# AK4493-Combi9.net
KiCad netlist of a schematic drawn in EAGLE
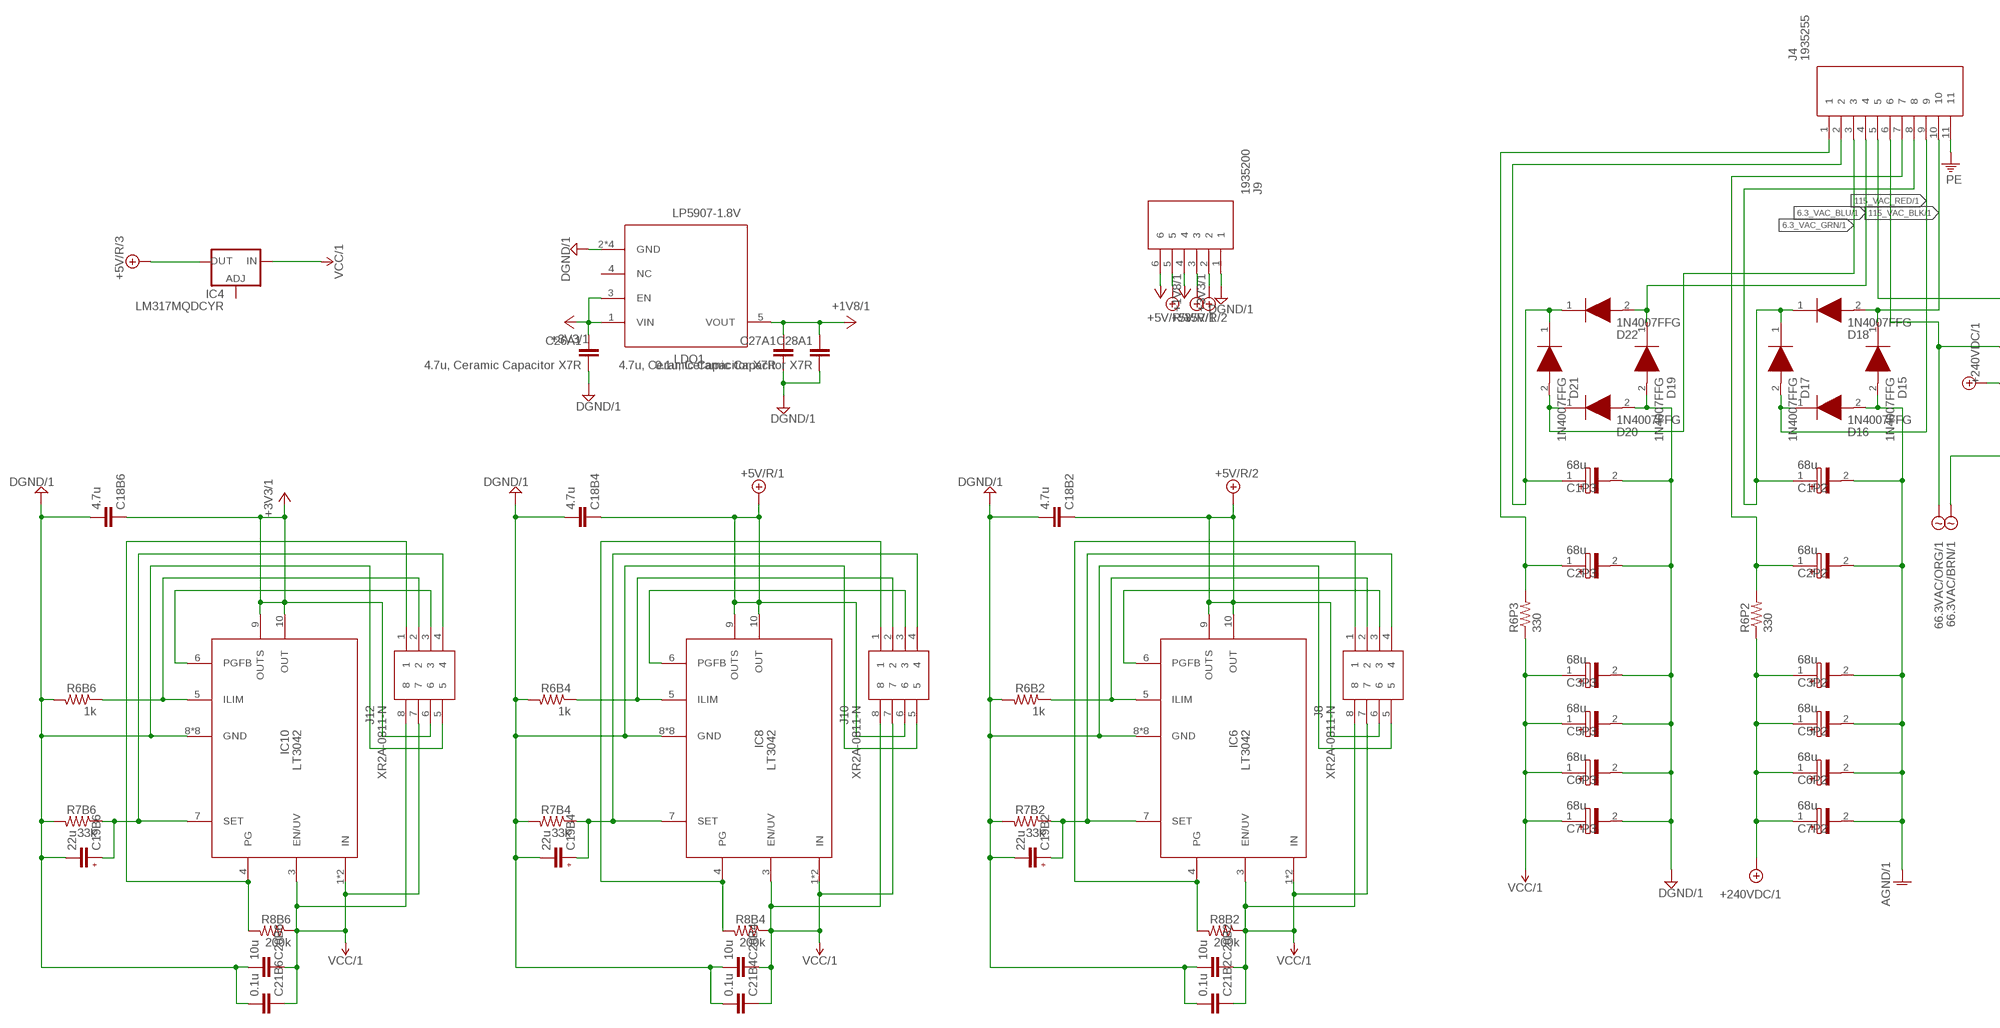
[diagram p0: schematic, sheet 1, part 1 of 3]
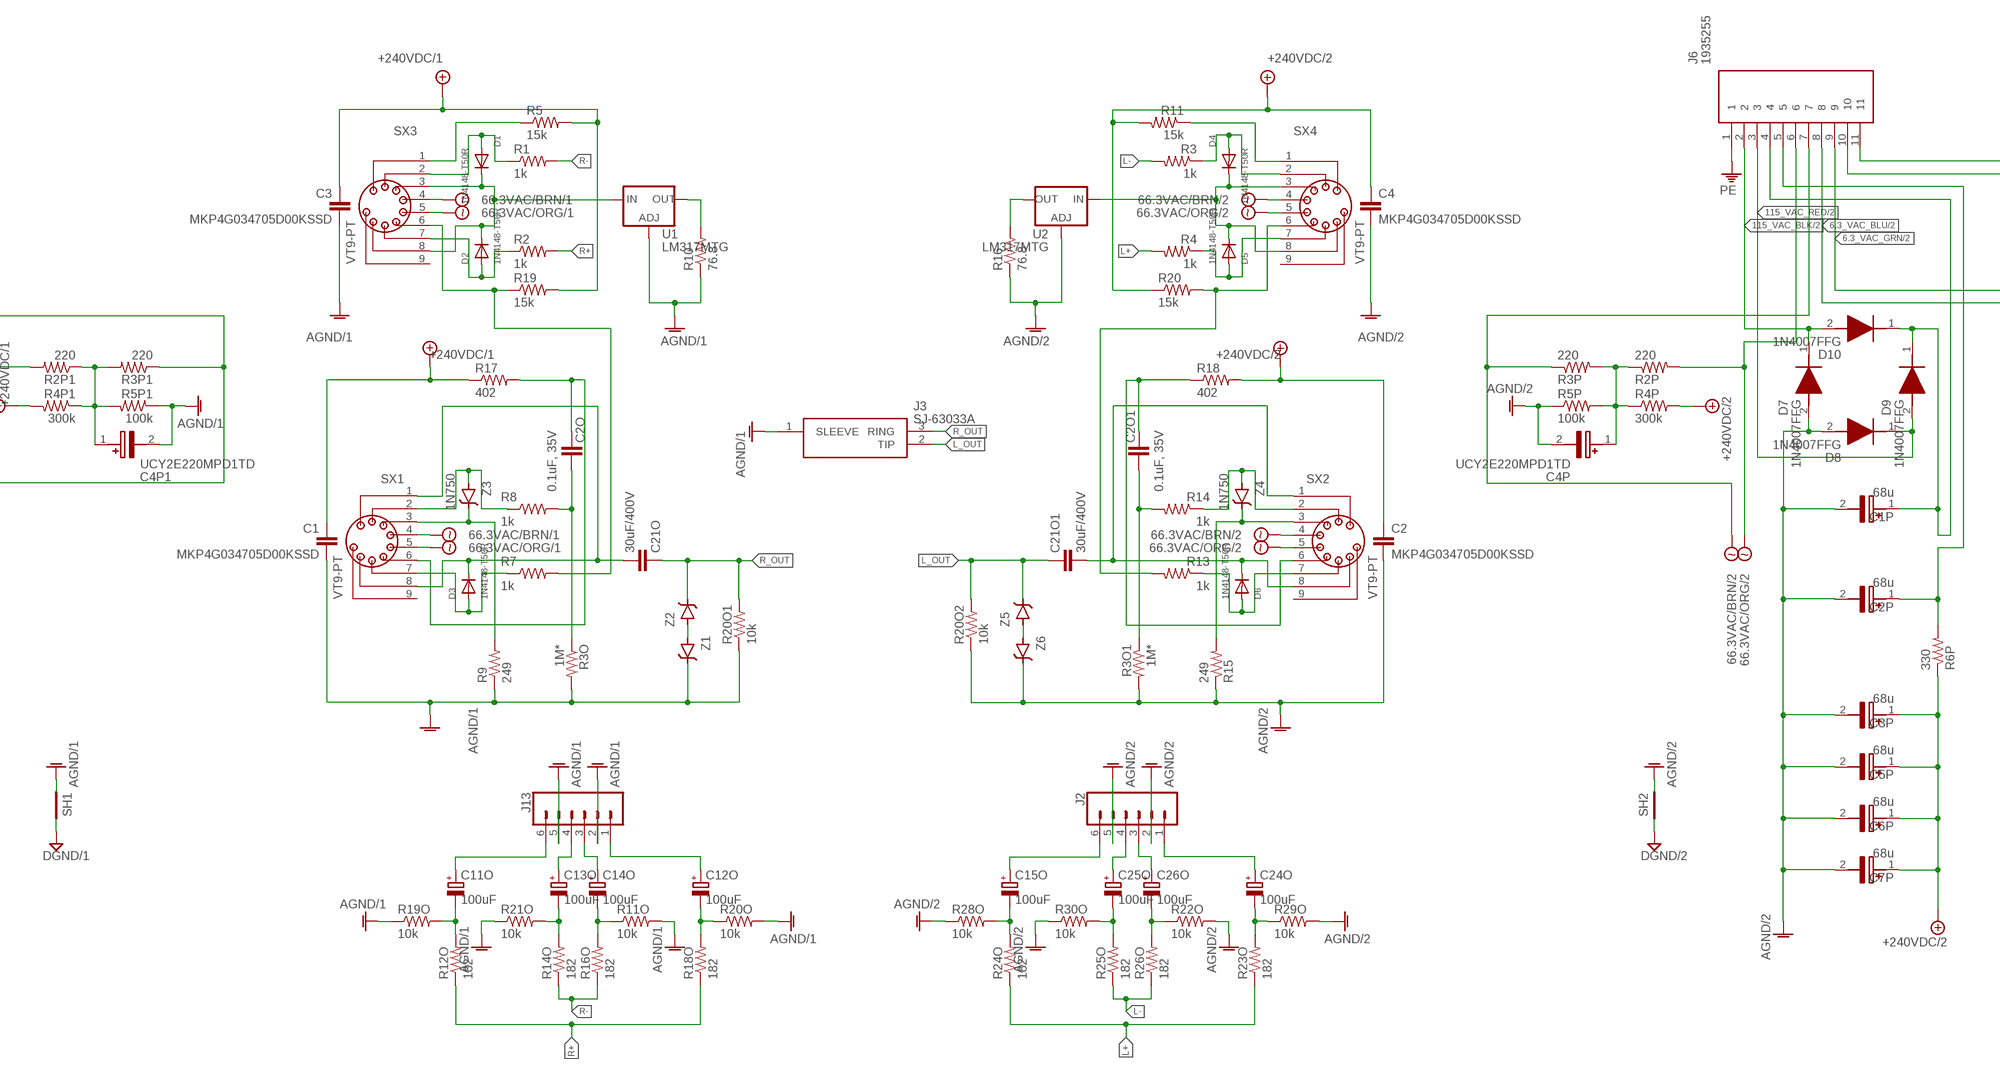
[diagram p1: schematic, sheet 1, part 2 of 3]
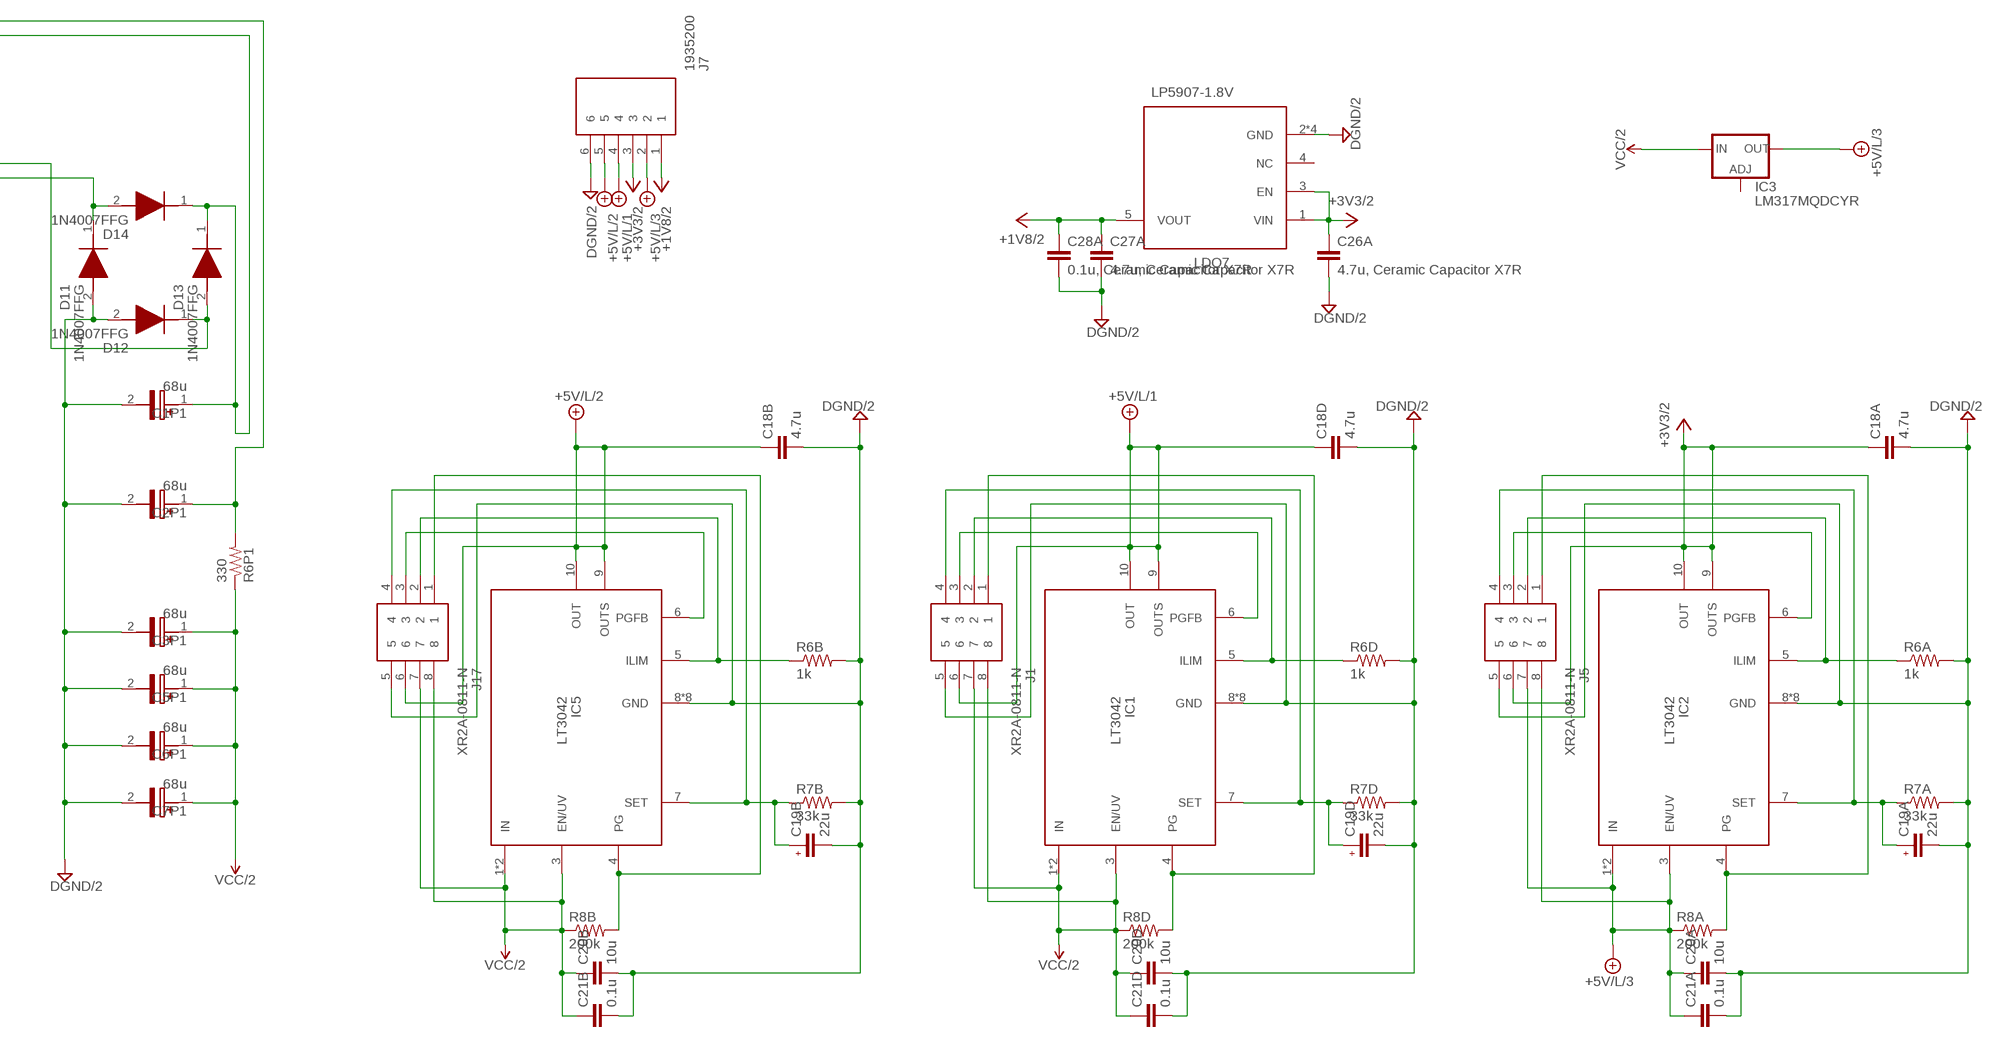
[diagram p2: schematic, sheet 1, part 3 of 3]

(export (version "E")
  (design (tool "Eeschema 10.0.6"))
  (components
    (comp (ref "C1")
      (value "MKP4G034705D00KSSD")
      (footprint "eagle-import:MKP4G034705D00KSSD")
      (fields (field (name "MOUSER_PART_NUMBER") "505-MKP4G034705DKSSD"))
      (libsource (lib "eagle-import") (part "MKP4G034705D00KSSD"))
    )
    (comp (ref "C1P")
      (value "68u")
      (footprint "eagle-import:CAPPRD750W80D1475H4700")
      (fields (field (name "MANUFACTURER_PART_NUMBER") "500HXW68MEFR14.5X45"))
      (libsource (lib "eagle-import") (part "500HXW68MEFR14.5X45"))
    )
    (comp (ref "C1P1")
      (value "68u")
      (footprint "eagle-import:CAPPRD750W80D1475H4700")
      (fields (field (name "MANUFACTURER_PART_NUMBER") "500HXW68MEFR14.5X45"))
      (libsource (lib "eagle-import") (part "500HXW68MEFR14.5X45"))
    )
    (comp (ref "C1P2")
      (value "68u")
      (footprint "eagle-import:CAPPRD750W80D1475H4700")
      (fields (field (name "MANUFACTURER_PART_NUMBER") "500HXW68MEFR14.5X45"))
      (libsource (lib "eagle-import") (part "500HXW68MEFR14.5X45"))
    )
    (comp (ref "C1P3")
      (value "68u")
      (footprint "eagle-import:CAPPRD750W80D1475H4700")
      (fields (field (name "MANUFACTURER_PART_NUMBER") "500HXW68MEFR14.5X45"))
      (libsource (lib "eagle-import") (part "500HXW68MEFR14.5X45"))
    )
    (comp (ref "C2")
      (value "MKP4G034705D00KSSD")
      (footprint "eagle-import:MKP4G034705D00KSSD")
      (fields (field (name "MOUSER_PART_NUMBER") "505-MKP4G034705DKSSD"))
      (libsource (lib "eagle-import") (part "MKP4G034705D00KSSD"))
    )
    (comp (ref "C2O")
      (value "0.1uF, 35V")
      (footprint "eagle-import:MKS4B031002A00JC00")
      (fields
        (field (name "MANUFACTURER_PART_NUMBER") "MKS4B031002A00JC00")
        (field (name "MOUSER_PART_NUMBER") "505-MKS4B0312AJC")
      )
      (libsource (lib "eagle-import") (part "MKS4B031002A00JC00"))
    )
    (comp (ref "C2O1")
      (value "0.1uF, 35V")
      (footprint "eagle-import:MKS4B031002A00JC00")
      (fields
        (field (name "MANUFACTURER_PART_NUMBER") "MKS4B031002A00JC00")
        (field (name "MOUSER_PART_NUMBER") "505-MKS4B0312AJC")
      )
      (libsource (lib "eagle-import") (part "MKS4B031002A00JC00"))
    )
    (comp (ref "C2P")
      (value "68u")
      (footprint "eagle-import:CAPPRD750W80D1475H4700")
      (fields (field (name "MANUFACTURER_PART_NUMBER") "500HXW68MEFR14.5X45"))
      (libsource (lib "eagle-import") (part "500HXW68MEFR14.5X45"))
    )
    (comp (ref "C2P1")
      (value "68u")
      (footprint "eagle-import:CAPPRD750W80D1475H4700")
      (fields (field (name "MANUFACTURER_PART_NUMBER") "500HXW68MEFR14.5X45"))
      (libsource (lib "eagle-import") (part "500HXW68MEFR14.5X45"))
    )
    (comp (ref "C2P2")
      (value "68u")
      (footprint "eagle-import:CAPPRD750W80D1475H4700")
      (fields (field (name "MANUFACTURER_PART_NUMBER") "500HXW68MEFR14.5X45"))
      (libsource (lib "eagle-import") (part "500HXW68MEFR14.5X45"))
    )
    (comp (ref "C2P3")
      (value "68u")
      (footprint "eagle-import:CAPPRD750W80D1475H4700")
      (fields (field (name "MANUFACTURER_PART_NUMBER") "500HXW68MEFR14.5X45"))
      (libsource (lib "eagle-import") (part "500HXW68MEFR14.5X45"))
    )
    (comp (ref "C3")
      (value "MKP4G034705D00KSSD")
      (footprint "eagle-import:MKP4G034705D00KSSD")
      (fields (field (name "MOUSER_PART_NUMBER") "505-MKP4G034705DKSSD"))
      (libsource (lib "eagle-import") (part "MKP4G034705D00KSSD"))
    )
    (comp (ref "C3P")
      (value "68u")
      (footprint "eagle-import:CAPPRD750W80D1475H4700")
      (fields (field (name "MANUFACTURER_PART_NUMBER") "500HXW68MEFR14.5X45"))
      (libsource (lib "eagle-import") (part "500HXW68MEFR14.5X45"))
    )
    (comp (ref "C3P1")
      (value "68u")
      (footprint "eagle-import:CAPPRD750W80D1475H4700")
      (fields (field (name "MANUFACTURER_PART_NUMBER") "500HXW68MEFR14.5X45"))
      (libsource (lib "eagle-import") (part "500HXW68MEFR14.5X45"))
    )
    (comp (ref "C3P2")
      (value "68u")
      (footprint "eagle-import:CAPPRD750W80D1475H4700")
      (fields (field (name "MANUFACTURER_PART_NUMBER") "500HXW68MEFR14.5X45"))
      (libsource (lib "eagle-import") (part "500HXW68MEFR14.5X45"))
    )
    (comp (ref "C3P3")
      (value "68u")
      (footprint "eagle-import:CAPPRD750W80D1475H4700")
      (fields (field (name "MANUFACTURER_PART_NUMBER") "500HXW68MEFR14.5X45"))
      (libsource (lib "eagle-import") (part "500HXW68MEFR14.5X45"))
    )
    (comp (ref "C4")
      (value "MKP4G034705D00KSSD")
      (footprint "eagle-import:MKP4G034705D00KSSD")
      (fields (field (name "MOUSER_PART_NUMBER") "505-MKP4G034705DKSSD"))
      (libsource (lib "eagle-import") (part "MKP4G034705D00KSSD"))
    )
    (comp (ref "C4P")
      (value "UCY2E220MPD1TD")
      (footprint "eagle-import:CAPPRD500W60D1025H1750")
      (fields (field (name "MOUSER_PART_NUMBER") "647-UCY2E220MPD1TD"))
      (libsource (lib "eagle-import") (part "UCY2E220MPD1TD"))
    )
    (comp (ref "C4P1")
      (value "UCY2E220MPD1TD")
      (footprint "eagle-import:CAPPRD500W60D1025H1750")
      (fields (field (name "MOUSER_PART_NUMBER") "647-UCY2E220MPD1TD"))
      (libsource (lib "eagle-import") (part "UCY2E220MPD1TD"))
    )
    (comp (ref "C5P")
      (value "68u")
      (footprint "eagle-import:CAPPRD750W80D1475H4700")
      (fields (field (name "MANUFACTURER_PART_NUMBER") "500HXW68MEFR14.5X45"))
      (libsource (lib "eagle-import") (part "500HXW68MEFR14.5X45"))
    )
    (comp (ref "C5P1")
      (value "68u")
      (footprint "eagle-import:CAPPRD750W80D1475H4700")
      (fields (field (name "MANUFACTURER_PART_NUMBER") "500HXW68MEFR14.5X45"))
      (libsource (lib "eagle-import") (part "500HXW68MEFR14.5X45"))
    )
    (comp (ref "C5P2")
      (value "68u")
      (footprint "eagle-import:CAPPRD750W80D1475H4700")
      (fields (field (name "MANUFACTURER_PART_NUMBER") "500HXW68MEFR14.5X45"))
      (libsource (lib "eagle-import") (part "500HXW68MEFR14.5X45"))
    )
    (comp (ref "C5P3")
      (value "68u")
      (footprint "eagle-import:CAPPRD750W80D1475H4700")
      (fields (field (name "MANUFACTURER_PART_NUMBER") "500HXW68MEFR14.5X45"))
      (libsource (lib "eagle-import") (part "500HXW68MEFR14.5X45"))
    )
    (comp (ref "C6P")
      (value "68u")
      (footprint "eagle-import:CAPPRD750W80D1475H4700")
      (fields (field (name "MANUFACTURER_PART_NUMBER") "500HXW68MEFR14.5X45"))
      (libsource (lib "eagle-import") (part "500HXW68MEFR14.5X45"))
    )
    (comp (ref "C6P1")
      (value "68u")
      (footprint "eagle-import:CAPPRD750W80D1475H4700")
      (fields (field (name "MANUFACTURER_PART_NUMBER") "500HXW68MEFR14.5X45"))
      (libsource (lib "eagle-import") (part "500HXW68MEFR14.5X45"))
    )
    (comp (ref "C6P2")
      (value "68u")
      (footprint "eagle-import:CAPPRD750W80D1475H4700")
      (fields (field (name "MANUFACTURER_PART_NUMBER") "500HXW68MEFR14.5X45"))
      (libsource (lib "eagle-import") (part "500HXW68MEFR14.5X45"))
    )
    (comp (ref "C6P3")
      (value "68u")
      (footprint "eagle-import:CAPPRD750W80D1475H4700")
      (fields (field (name "MANUFACTURER_PART_NUMBER") "500HXW68MEFR14.5X45"))
      (libsource (lib "eagle-import") (part "500HXW68MEFR14.5X45"))
    )
    (comp (ref "C7P")
      (value "68u")
      (footprint "eagle-import:CAPPRD750W80D1475H4700")
      (fields (field (name "MANUFACTURER_PART_NUMBER") "500HXW68MEFR14.5X45"))
      (libsource (lib "eagle-import") (part "500HXW68MEFR14.5X45"))
    )
    (comp (ref "C7P1")
      (value "68u")
      (footprint "eagle-import:CAPPRD750W80D1475H4700")
      (fields (field (name "MANUFACTURER_PART_NUMBER") "500HXW68MEFR14.5X45"))
      (libsource (lib "eagle-import") (part "500HXW68MEFR14.5X45"))
    )
    (comp (ref "C7P2")
      (value "68u")
      (footprint "eagle-import:CAPPRD750W80D1475H4700")
      (fields (field (name "MANUFACTURER_PART_NUMBER") "500HXW68MEFR14.5X45"))
      (libsource (lib "eagle-import") (part "500HXW68MEFR14.5X45"))
    )
    (comp (ref "C7P3")
      (value "68u")
      (footprint "eagle-import:CAPPRD750W80D1475H4700")
      (fields (field (name "MANUFACTURER_PART_NUMBER") "500HXW68MEFR14.5X45"))
      (libsource (lib "eagle-import") (part "500HXW68MEFR14.5X45"))
    )
    (comp (ref "C11O")
      (value "100uF")
      (footprint "eagle-import:CAPPRD350W60D825H1300")
      (fields
        (field (name "ARROW_PART_NUMBER") "UFW1H101MPD1TD")
        (field (name "MOUSER_PART_NUMBER") "647-UFW1H101MPD1TD")
      )
      (libsource (lib "eagle-import") (part "UFW1H101MPD1TD"))
    )
    (comp (ref "C12O")
      (value "100uF")
      (footprint "eagle-import:CAPPRD350W60D825H1300")
      (fields
        (field (name "ARROW_PART_NUMBER") "UFW1H101MPD1TD")
        (field (name "MOUSER_PART_NUMBER") "647-UFW1H101MPD1TD")
      )
      (libsource (lib "eagle-import") (part "UFW1H101MPD1TD"))
    )
    (comp (ref "C13O")
      (value "100uF")
      (footprint "eagle-import:CAPPRD350W60D825H1300")
      (fields
        (field (name "ARROW_PART_NUMBER") "UFW1H101MPD1TD")
        (field (name "MOUSER_PART_NUMBER") "647-UFW1H101MPD1TD")
      )
      (libsource (lib "eagle-import") (part "UFW1H101MPD1TD"))
    )
    (comp (ref "C14O")
      (value "100uF")
      (footprint "eagle-import:CAPPRD350W60D825H1300")
      (fields
        (field (name "ARROW_PART_NUMBER") "UFW1H101MPD1TD")
        (field (name "MOUSER_PART_NUMBER") "647-UFW1H101MPD1TD")
      )
      (libsource (lib "eagle-import") (part "UFW1H101MPD1TD"))
    )
    (comp (ref "C15O")
      (value "100uF")
      (footprint "eagle-import:CAPPRD350W60D825H1300")
      (fields
        (field (name "ARROW_PART_NUMBER") "UFW1H101MPD1TD")
        (field (name "MOUSER_PART_NUMBER") "647-UFW1H101MPD1TD")
      )
      (libsource (lib "eagle-import") (part "UFW1H101MPD1TD"))
    )
    (comp (ref "C18A")
      (value "4.7u")
      (footprint "eagle-import:CAPC2013X140N")
      (fields
        (field (name "MANUFACTURER_PART_NUMBER") "EMK212ABJ475KG-T")
        (field (name "MOUSER_PART_NUMBER") "963-EMK212ABJ475KG-T")
      )
      (libsource (lib "eagle-import") (part "EMK212ABJ475KG-T"))
    )
    (comp (ref "C18B")
      (value "4.7u")
      (footprint "eagle-import:CAPC2013X140N")
      (fields
        (field (name "MANUFACTURER_PART_NUMBER") "EMK212ABJ475KG-T")
        (field (name "MOUSER_PART_NUMBER") "963-EMK212ABJ475KG-T")
      )
      (libsource (lib "eagle-import") (part "EMK212ABJ475KG-T"))
    )
    (comp (ref "C18B2")
      (value "4.7u")
      (footprint "eagle-import:CAPC2013X140N")
      (fields
        (field (name "MANUFACTURER_PART_NUMBER") "EMK212ABJ475KG-T")
        (field (name "MOUSER_PART_NUMBER") "963-EMK212ABJ475KG-T")
      )
      (libsource (lib "eagle-import") (part "EMK212ABJ475KG-T"))
    )
    (comp (ref "C18B4")
      (value "4.7u")
      (footprint "eagle-import:CAPC2013X140N")
      (fields
        (field (name "MANUFACTURER_PART_NUMBER") "EMK212ABJ475KG-T")
        (field (name "MOUSER_PART_NUMBER") "963-EMK212ABJ475KG-T")
      )
      (libsource (lib "eagle-import") (part "EMK212ABJ475KG-T"))
    )
    (comp (ref "C18B6")
      (value "4.7u")
      (footprint "eagle-import:CAPC2013X140N")
      (fields
        (field (name "MANUFACTURER_PART_NUMBER") "EMK212ABJ475KG-T")
        (field (name "MOUSER_PART_NUMBER") "963-EMK212ABJ475KG-T")
      )
      (libsource (lib "eagle-import") (part "EMK212ABJ475KG-T"))
    )
    (comp (ref "C18D")
      (value "4.7u")
      (footprint "eagle-import:CAPC2013X140N")
      (fields
        (field (name "MANUFACTURER_PART_NUMBER") "EMK212ABJ475KG-T")
        (field (name "MOUSER_PART_NUMBER") "963-EMK212ABJ475KG-T")
      )
      (libsource (lib "eagle-import") (part "EMK212ABJ475KG-T"))
    )
    (comp (ref "C19A")
      (value "22u")
      (footprint "eagle-import:C1206")
      (fields
        (field (name "MANUFACTURER_PART_NUMBER") "EMK316BB7226ML-T")
        (field (name "MOUSER_PART_NUMBER") "963-EMK316BB7226ML-T")
      )
      (libsource (lib "eagle-import") (part "EMK316BB7226ML-T"))
    )
    (comp (ref "C19B")
      (value "22u")
      (footprint "eagle-import:C1206")
      (fields
        (field (name "MANUFACTURER_PART_NUMBER") "EMK316BB7226ML-T")
        (field (name "MOUSER_PART_NUMBER") "963-EMK316BB7226ML-T")
      )
      (libsource (lib "eagle-import") (part "EMK316BB7226ML-T"))
    )
    (comp (ref "C19B2")
      (value "22u")
      (footprint "eagle-import:C1206")
      (fields
        (field (name "MANUFACTURER_PART_NUMBER") "EMK316BB7226ML-T")
        (field (name "MOUSER_PART_NUMBER") "963-EMK316BB7226ML-T")
      )
      (libsource (lib "eagle-import") (part "EMK316BB7226ML-T"))
    )
    (comp (ref "C19B4")
      (value "22u")
      (footprint "eagle-import:C1206")
      (fields
        (field (name "MANUFACTURER_PART_NUMBER") "EMK316BB7226ML-T")
        (field (name "MOUSER_PART_NUMBER") "963-EMK316BB7226ML-T")
      )
      (libsource (lib "eagle-import") (part "EMK316BB7226ML-T"))
    )
    (comp (ref "C19B6")
      (value "22u")
      (footprint "eagle-import:C1206")
      (fields
        (field (name "MANUFACTURER_PART_NUMBER") "EMK316BB7226ML-T")
        (field (name "MOUSER_PART_NUMBER") "963-EMK316BB7226ML-T")
      )
      (libsource (lib "eagle-import") (part "EMK316BB7226ML-T"))
    )
    (comp (ref "C19D")
      (value "22u")
      (footprint "eagle-import:C1206")
      (fields
        (field (name "MANUFACTURER_PART_NUMBER") "EMK316BB7226ML-T")
        (field (name "MOUSER_PART_NUMBER") "963-EMK316BB7226ML-T")
      )
      (libsource (lib "eagle-import") (part "EMK316BB7226ML-T"))
    )
    (comp (ref "C20A")
      (value "10u")
      (footprint "eagle-import:CAPC2012X135N")
      (fields
        (field (name "MANUFACTURER_PART_NUMBER") "EMK212BB7106KG-T")
        (field (name "MOUSER_PART_NUMBER") "963-EMK212BB7106KG-T")
      )
      (libsource (lib "eagle-import") (part "EMK212BB7106KG-T"))
    )
    (comp (ref "C20B")
      (value "10u")
      (footprint "eagle-import:CAPC2012X135N")
      (fields
        (field (name "MANUFACTURER_PART_NUMBER") "EMK212BB7106KG-T")
        (field (name "MOUSER_PART_NUMBER") "963-EMK212BB7106KG-T")
      )
      (libsource (lib "eagle-import") (part "EMK212BB7106KG-T"))
    )
    (comp (ref "C20B2")
      (value "10u")
      (footprint "eagle-import:CAPC2012X135N")
      (fields
        (field (name "MANUFACTURER_PART_NUMBER") "EMK212BB7106KG-T")
        (field (name "MOUSER_PART_NUMBER") "963-EMK212BB7106KG-T")
      )
      (libsource (lib "eagle-import") (part "EMK212BB7106KG-T"))
    )
    (comp (ref "C20B4")
      (value "10u")
      (footprint "eagle-import:CAPC2012X135N")
      (fields
        (field (name "MANUFACTURER_PART_NUMBER") "EMK212BB7106KG-T")
        (field (name "MOUSER_PART_NUMBER") "963-EMK212BB7106KG-T")
      )
      (libsource (lib "eagle-import") (part "EMK212BB7106KG-T"))
    )
    (comp (ref "C20B6")
      (value "10u")
      (footprint "eagle-import:CAPC2012X135N")
      (fields
        (field (name "MANUFACTURER_PART_NUMBER") "EMK212BB7106KG-T")
        (field (name "MOUSER_PART_NUMBER") "963-EMK212BB7106KG-T")
      )
      (libsource (lib "eagle-import") (part "EMK212BB7106KG-T"))
    )
    (comp (ref "C20D")
      (value "10u")
      (footprint "eagle-import:CAPC2012X135N")
      (fields
        (field (name "MANUFACTURER_PART_NUMBER") "EMK212BB7106KG-T")
        (field (name "MOUSER_PART_NUMBER") "963-EMK212BB7106KG-T")
      )
      (libsource (lib "eagle-import") (part "EMK212BB7106KG-T"))
    )
    (comp (ref "C21A")
      (value "0.1u")
      (footprint "eagle-import:CAPC2012X135N")
      (fields
        (field (name "MANUFACTURER_PART_NUMBER") "EMF212B7104KGHT")
        (field (name "MOUSER_PART_NUMBER") "963-EMF212B7104KGHT")
      )
      (libsource (lib "eagle-import") (part "EMF212B7104KGHT"))
    )
    (comp (ref "C21B")
      (value "0.1u")
      (footprint "eagle-import:CAPC2012X135N")
      (fields
        (field (name "MANUFACTURER_PART_NUMBER") "EMF212B7104KGHT")
        (field (name "MOUSER_PART_NUMBER") "963-EMF212B7104KGHT")
      )
      (libsource (lib "eagle-import") (part "EMF212B7104KGHT"))
    )
    (comp (ref "C21B2")
      (value "0.1u")
      (footprint "eagle-import:CAPC2012X135N")
      (fields
        (field (name "MANUFACTURER_PART_NUMBER") "EMF212B7104KGHT")
        (field (name "MOUSER_PART_NUMBER") "963-EMF212B7104KGHT")
      )
      (libsource (lib "eagle-import") (part "EMF212B7104KGHT"))
    )
    (comp (ref "C21B4")
      (value "0.1u")
      (footprint "eagle-import:CAPC2012X135N")
      (fields
        (field (name "MANUFACTURER_PART_NUMBER") "EMF212B7104KGHT")
        (field (name "MOUSER_PART_NUMBER") "963-EMF212B7104KGHT")
      )
      (libsource (lib "eagle-import") (part "EMF212B7104KGHT"))
    )
    (comp (ref "C21B6")
      (value "0.1u")
      (footprint "eagle-import:CAPC2012X135N")
      (fields
        (field (name "MANUFACTURER_PART_NUMBER") "EMF212B7104KGHT")
        (field (name "MOUSER_PART_NUMBER") "963-EMF212B7104KGHT")
      )
      (libsource (lib "eagle-import") (part "EMF212B7104KGHT"))
    )
    (comp (ref "C21D")
      (value "0.1u")
      (footprint "eagle-import:CAPC2012X135N")
      (fields
        (field (name "MANUFACTURER_PART_NUMBER") "EMF212B7104KGHT")
        (field (name "MOUSER_PART_NUMBER") "963-EMF212B7104KGHT")
      )
      (libsource (lib "eagle-import") (part "EMF212B7104KGHT"))
    )
    (comp (ref "C21O")
      (value "30uF/400V")
      (footprint "eagle-import:DCP4G056007GD4KSSD")
      (fields
        (field (name "MANUFACTURER_PART_NUMBER") "DCP4G056007GD4KSSD")
        (field (name "MOUSER_PART_NUMBER") "505-DCP4G056007GD4KS")
      )
      (libsource (lib "eagle-import") (part "DCP4G056007GD4KSSD"))
    )
    (comp (ref "C21O1")
      (value "30uF/400V")
      (footprint "eagle-import:DCP4G056007GD4KSSD")
      (fields
        (field (name "MANUFACTURER_PART_NUMBER") "DCP4G056007GD4KSSD")
        (field (name "MOUSER_PART_NUMBER") "505-DCP4G056007GD4KS")
      )
      (libsource (lib "eagle-import") (part "DCP4G056007GD4KSSD"))
    )
    (comp (ref "C24O")
      (value "100uF")
      (footprint "eagle-import:CAPPRD350W60D825H1300")
      (fields
        (field (name "ARROW_PART_NUMBER") "UFW1H101MPD1TD")
        (field (name "MOUSER_PART_NUMBER") "647-UFW1H101MPD1TD")
      )
      (libsource (lib "eagle-import") (part "UFW1H101MPD1TD"))
    )
    (comp (ref "C25O")
      (value "100uF")
      (footprint "eagle-import:CAPPRD350W60D825H1300")
      (fields
        (field (name "ARROW_PART_NUMBER") "UFW1H101MPD1TD")
        (field (name "MOUSER_PART_NUMBER") "647-UFW1H101MPD1TD")
      )
      (libsource (lib "eagle-import") (part "UFW1H101MPD1TD"))
    )
    (comp (ref "C26A")
      (value "4.7u, Ceramic Capacitor X7R")
      (footprint "eagle-import:CAPC2013X140N")
      (fields
        (field (name "MANUFACTURER_PART_NUMBER") "EMK212ABJ475KG-T")
        (field (name "MOUSER_PART_NUMBER") "963-EMK212ABJ475KG-T")
      )
      (libsource (lib "eagle-import") (part "EMK212ABJ475KG-T"))
    )
    (comp (ref "C26A1")
      (value "4.7u, Ceramic Capacitor X7R")
      (footprint "eagle-import:CAPC2013X140N")
      (fields
        (field (name "MANUFACTURER_PART_NUMBER") "EMK212ABJ475KG-T")
        (field (name "MOUSER_PART_NUMBER") "963-EMK212ABJ475KG-T")
      )
      (libsource (lib "eagle-import") (part "EMK212ABJ475KG-T"))
    )
    (comp (ref "C26O")
      (value "100uF")
      (footprint "eagle-import:CAPPRD350W60D825H1300")
      (fields
        (field (name "ARROW_PART_NUMBER") "UFW1H101MPD1TD")
        (field (name "MOUSER_PART_NUMBER") "647-UFW1H101MPD1TD")
      )
      (libsource (lib "eagle-import") (part "UFW1H101MPD1TD"))
    )
    (comp (ref "C27A")
      (value "4.7u, Ceramic Capacitor X7R")
      (footprint "eagle-import:CAPC2013X140N")
      (fields
        (field (name "MANUFACTURER_PART_NUMBER") "EMK212ABJ475KG-T")
        (field (name "MOUSER_PART_NUMBER") "963-EMK212ABJ475KG-T")
      )
      (libsource (lib "eagle-import") (part "EMK212ABJ475KG-T"))
    )
    (comp (ref "C27A1")
      (value "4.7u, Ceramic Capacitor X7R")
      (footprint "eagle-import:CAPC2013X140N")
      (fields
        (field (name "MANUFACTURER_PART_NUMBER") "EMK212ABJ475KG-T")
        (field (name "MOUSER_PART_NUMBER") "963-EMK212ABJ475KG-T")
      )
      (libsource (lib "eagle-import") (part "EMK212ABJ475KG-T"))
    )
    (comp (ref "C28A")
      (value "0.1u, Ceramic Capacitor X7R")
      (footprint "eagle-import:CAPC2012X135N")
      (fields
        (field (name "MANUFACTURER_PART_NUMBER") "EMF212B7104KGHT")
        (field (name "MOUSER_PART_NUMBER") "963-EMF212B7104KGHT")
      )
      (libsource (lib "eagle-import") (part "EMF212B7104KGHT"))
    )
    (comp (ref "C28A1")
      (value "0.1u, Ceramic Capacitor X7R")
      (footprint "eagle-import:CAPC2012X135N")
      (fields
        (field (name "MANUFACTURER_PART_NUMBER") "EMF212B7104KGHT")
        (field (name "MOUSER_PART_NUMBER") "963-EMF212B7104KGHT")
      )
      (libsource (lib "eagle-import") (part "EMF212B7104KGHT"))
    )
    (comp (ref "D1")
      (value "1N4148-T50R")
      (footprint "eagle-import:DIOAD1068W53L380D172")
      (fields (field (name "MOUSER_PART_NUMBER") "512-1N4148T50R"))
      (libsource (lib "eagle-import") (part "1N4148-T50R"))
    )
    (comp (ref "D2")
      (value "1N4148-T50R")
      (footprint "eagle-import:DIOAD1068W53L380D172")
      (fields (field (name "MOUSER_PART_NUMBER") "512-1N4148T50R"))
      (libsource (lib "eagle-import") (part "1N4148-T50R"))
    )
    (comp (ref "D3")
      (value "1N4148-T50R")
      (footprint "eagle-import:DIOAD1068W53L380D172")
      (fields (field (name "MOUSER_PART_NUMBER") "512-1N4148T50R"))
      (libsource (lib "eagle-import") (part "1N4148-T50R"))
    )
    (comp (ref "D4")
      (value "1N4148-T50R")
      (footprint "eagle-import:DIOAD1068W53L380D172")
      (fields (field (name "MOUSER_PART_NUMBER") "512-1N4148T50R"))
      (libsource (lib "eagle-import") (part "1N4148-T50R"))
    )
    (comp (ref "D5")
      (value "1N4148-T50R")
      (footprint "eagle-import:DIOAD1068W53L380D172")
      (fields (field (name "MOUSER_PART_NUMBER") "512-1N4148T50R"))
      (libsource (lib "eagle-import") (part "1N4148-T50R"))
    )
    (comp (ref "D6")
      (value "1N4148-T50R")
      (footprint "eagle-import:DIOAD1068W53L380D172")
      (fields (field (name "MOUSER_PART_NUMBER") "512-1N4148T50R"))
      (libsource (lib "eagle-import") (part "1N4148-T50R"))
    )
    (comp (ref "D7")
      (value "1N4007FFG")
      (footprint "eagle-import:DIOAD1405W86L465D235")
      (fields (field (name "MOUSER_PART_NUMBER") "863-1N4007FFG"))
      (libsource (lib "eagle-import") (part "1N4007FFG"))
    )
    (comp (ref "D8")
      (value "1N4007FFG")
      (footprint "eagle-import:DIOAD1405W86L465D235")
      (fields (field (name "MOUSER_PART_NUMBER") "863-1N4007FFG"))
      (libsource (lib "eagle-import") (part "1N4007FFG"))
    )
    (comp (ref "D9")
      (value "1N4007FFG")
      (footprint "eagle-import:DIOAD1405W86L465D235")
      (fields (field (name "MOUSER_PART_NUMBER") "863-1N4007FFG"))
      (libsource (lib "eagle-import") (part "1N4007FFG"))
    )
    (comp (ref "D10")
      (value "1N4007FFG")
      (footprint "eagle-import:DIOAD1405W86L465D235")
      (fields (field (name "MOUSER_PART_NUMBER") "863-1N4007FFG"))
      (libsource (lib "eagle-import") (part "1N4007FFG"))
    )
    (comp (ref "D11")
      (value "1N4007FFG")
      (footprint "eagle-import:DIOAD1405W86L465D235")
      (fields (field (name "MOUSER_PART_NUMBER") "863-1N4007FFG"))
      (libsource (lib "eagle-import") (part "1N4007FFG"))
    )
    (comp (ref "D12")
      (value "1N4007FFG")
      (footprint "eagle-import:DIOAD1405W86L465D235")
      (fields (field (name "MOUSER_PART_NUMBER") "863-1N4007FFG"))
      (libsource (lib "eagle-import") (part "1N4007FFG"))
    )
    (comp (ref "D13")
      (value "1N4007FFG")
      (footprint "eagle-import:DIOAD1405W86L465D235")
      (fields (field (name "MOUSER_PART_NUMBER") "863-1N4007FFG"))
      (libsource (lib "eagle-import") (part "1N4007FFG"))
    )
    (comp (ref "D14")
      (value "1N4007FFG")
      (footprint "eagle-import:DIOAD1405W86L465D235")
      (fields (field (name "MOUSER_PART_NUMBER") "863-1N4007FFG"))
      (libsource (lib "eagle-import") (part "1N4007FFG"))
    )
    (comp (ref "D15")
      (value "1N4007FFG")
      (footprint "eagle-import:DIOAD1405W86L465D235")
      (fields (field (name "MOUSER_PART_NUMBER") "863-1N4007FFG"))
      (libsource (lib "eagle-import") (part "1N4007FFG"))
    )
    (comp (ref "D16")
      (value "1N4007FFG")
      (footprint "eagle-import:DIOAD1405W86L465D235")
      (fields (field (name "MOUSER_PART_NUMBER") "863-1N4007FFG"))
      (libsource (lib "eagle-import") (part "1N4007FFG"))
    )
    (comp (ref "D17")
      (value "1N4007FFG")
      (footprint "eagle-import:DIOAD1405W86L465D235")
      (fields (field (name "MOUSER_PART_NUMBER") "863-1N4007FFG"))
      (libsource (lib "eagle-import") (part "1N4007FFG"))
    )
    (comp (ref "D18")
      (value "1N4007FFG")
      (footprint "eagle-import:DIOAD1405W86L465D235")
      (fields (field (name "MOUSER_PART_NUMBER") "863-1N4007FFG"))
      (libsource (lib "eagle-import") (part "1N4007FFG"))
    )
    (comp (ref "D19")
      (value "1N4007FFG")
      (footprint "eagle-import:DIOAD1405W86L465D235")
      (fields (field (name "MOUSER_PART_NUMBER") "863-1N4007FFG"))
      (libsource (lib "eagle-import") (part "1N4007FFG"))
    )
    (comp (ref "D20")
      (value "1N4007FFG")
      (footprint "eagle-import:DIOAD1405W86L465D235")
      (fields (field (name "MOUSER_PART_NUMBER") "863-1N4007FFG"))
      (libsource (lib "eagle-import") (part "1N4007FFG"))
    )
    (comp (ref "D21")
      (value "1N4007FFG")
      (footprint "eagle-import:DIOAD1405W86L465D235")
      (fields (field (name "MOUSER_PART_NUMBER") "863-1N4007FFG"))
      (libsource (lib "eagle-import") (part "1N4007FFG"))
    )
    (comp (ref "D22")
      (value "1N4007FFG")
      (footprint "eagle-import:DIOAD1405W86L465D235")
      (fields (field (name "MOUSER_PART_NUMBER") "863-1N4007FFG"))
      (libsource (lib "eagle-import") (part "1N4007FFG"))
    )
    (comp (ref "IC1")
      (value "LT3042")
      (footprint "eagle-import:SOP50P490X110-11N")
      (fields
        (field (name "MANUFACTURER_PART_NUMBER") "LT3042EMSE#PBF")
        (field (name "MOUSER_PART_NUMBER") "584-LT3042EMSE#PBF")
      )
      (libsource (lib "eagle-import") (part "LT3042"))
    )
    (comp (ref "IC2")
      (value "LT3042")
      (footprint "eagle-import:SOP50P490X110-11N")
      (fields
        (field (name "MANUFACTURER_PART_NUMBER") "LT3042EMSE#PBF")
        (field (name "MOUSER_PART_NUMBER") "584-LT3042EMSE#PBF")
      )
      (libsource (lib "eagle-import") (part "LT3042"))
    )
    (comp (ref "IC3")
      (value "LM317MQDCYR")
      (footprint "eagle-import:SOT230P700X180-4N")
      (fields (field (name "MOUSER_PART_NUMBER") "595-LM317MQDCYR"))
      (libsource (lib "eagle-import") (part "LM317MQDCYR"))
    )
    (comp (ref "IC4")
      (value "LM317MQDCYR")
      (footprint "eagle-import:SOT230P700X180-4N")
      (fields (field (name "MOUSER_PART_NUMBER") "595-LM317MQDCYR"))
      (libsource (lib "eagle-import") (part "LM317MQDCYR"))
    )
    (comp (ref "IC5")
      (value "LT3042")
      (footprint "eagle-import:SOP50P490X110-11N")
      (fields
        (field (name "MANUFACTURER_PART_NUMBER") "LT3042EMSE#PBF")
        (field (name "MOUSER_PART_NUMBER") "584-LT3042EMSE#PBF")
      )
      (libsource (lib "eagle-import") (part "LT3042"))
    )
    (comp (ref "IC6")
      (value "LT3042")
      (footprint "eagle-import:SOP50P490X110-11N")
      (fields
        (field (name "MANUFACTURER_PART_NUMBER") "LT3042EMSE#PBF")
        (field (name "MOUSER_PART_NUMBER") "584-LT3042EMSE#PBF")
      )
      (libsource (lib "eagle-import") (part "LT3042"))
    )
    (comp (ref "IC8")
      (value "LT3042")
      (footprint "eagle-import:SOP50P490X110-11N")
      (fields
        (field (name "MANUFACTURER_PART_NUMBER") "LT3042EMSE#PBF")
        (field (name "MOUSER_PART_NUMBER") "584-LT3042EMSE#PBF")
      )
      (libsource (lib "eagle-import") (part "LT3042"))
    )
    (comp (ref "IC10")
      (value "LT3042")
      (footprint "eagle-import:SOP50P490X110-11N")
      (fields
        (field (name "MANUFACTURER_PART_NUMBER") "LT3042EMSE#PBF")
        (field (name "MOUSER_PART_NUMBER") "584-LT3042EMSE#PBF")
      )
      (libsource (lib "eagle-import") (part "LT3042"))
    )
    (comp (ref "J1")
      (value "XR2A-0811-N")
      (footprint "eagle-import:DIPS762W51P254L1016H390Q8N")
      (fields (field (name "MOUSER_PART_NUMBER") "653-XR2A-0811-N"))
      (libsource (lib "eagle-import") (part "XR2A-0811-N"))
    )
    (comp (ref "J2")
      (value "CONN_06SILK_FEMALE_PTH")
      (footprint "eagle-import:1X06")
      (libsource (lib "eagle-import") (part "CONN_06SILK_FEMALE_PTH"))
    )
    (comp (ref "J3")
      (value "SJ-63033A")
      (footprint "eagle-import:SJ63033A")
      (libsource (lib "eagle-import") (part "SJ-63033A"))
    )
    (comp (ref "J4")
      (value "1935255")
      (footprint "eagle-import:1935255")
      (fields (field (name "MOUSER_PART_NUMBER") "651-1935255"))
      (libsource (lib "eagle-import") (part "1935255"))
    )
    (comp (ref "J5")
      (value "XR2A-0811-N")
      (footprint "eagle-import:DIPS762W51P254L1016H390Q8N")
      (fields (field (name "MOUSER_PART_NUMBER") "653-XR2A-0811-N"))
      (libsource (lib "eagle-import") (part "XR2A-0811-N"))
    )
    (comp (ref "J6")
      (value "1935255")
      (footprint "eagle-import:1935255")
      (fields (field (name "MOUSER_PART_NUMBER") "651-1935255"))
      (libsource (lib "eagle-import") (part "Dual Mono Amp Library_47621477_1935255"))
    )
    (comp (ref "J7")
      (value "1935200")
      (footprint "eagle-import:1935200")
      (fields (field (name "MOUSER_PART_NUMBER") "651-1935200"))
      (libsource (lib "eagle-import") (part "Dual Mono Amp Library_47621477_1935200"))
    )
    (comp (ref "J8")
      (value "XR2A-0811-N")
      (footprint "eagle-import:DIPS762W51P254L1016H390Q8N")
      (fields (field (name "MOUSER_PART_NUMBER") "653-XR2A-0811-N"))
      (libsource (lib "eagle-import") (part "XR2A-0811-N"))
    )
    (comp (ref "J9")
      (value "1935200")
      (footprint "eagle-import:1935200")
      (fields (field (name "MOUSER_PART_NUMBER") "651-1935200"))
      (libsource (lib "eagle-import") (part "1935200"))
    )
    (comp (ref "J10")
      (value "XR2A-0811-N")
      (footprint "eagle-import:DIPS762W51P254L1016H390Q8N")
      (fields (field (name "MOUSER_PART_NUMBER") "653-XR2A-0811-N"))
      (libsource (lib "eagle-import") (part "XR2A-0811-N"))
    )
    (comp (ref "J12")
      (value "XR2A-0811-N")
      (footprint "eagle-import:DIPS762W51P254L1016H390Q8N")
      (fields (field (name "MOUSER_PART_NUMBER") "653-XR2A-0811-N"))
      (libsource (lib "eagle-import") (part "XR2A-0811-N"))
    )
    (comp (ref "J13")
      (value "CONN_06SILK_FEMALE_PTH")
      (footprint "eagle-import:1X06")
      (libsource (lib "eagle-import") (part "CONN_06SILK_FEMALE_PTH"))
    )
    (comp (ref "J17")
      (value "XR2A-0811-N")
      (footprint "eagle-import:DIPS762W51P254L1016H390Q8N")
      (fields (field (name "MOUSER_PART_NUMBER") "653-XR2A-0811-N"))
      (libsource (lib "eagle-import") (part "XR2A-0811-N"))
    )
    (comp (ref "LDO1")
      (value "LP5907-1.8V")
      (footprint "eagle-import:SOT95P280X145-5N")
      (fields
        (field (name "ARROW_PART_NUMBER") "LP5907MFX-1.8/NOPB")
        (field (name "MOUSER_PART_NUMBER") "595-LP5907MFX-1.8NPB")
      )
      (libsource (lib "eagle-import") (part "LP5907-1.8V"))
    )
    (comp (ref "LDO7")
      (value "LP5907-1.8V")
      (footprint "eagle-import:SOT95P280X145-5N")
      (fields
        (field (name "ARROW_PART_NUMBER") "LP5907MFX-1.8/NOPB")
        (field (name "MOUSER_PART_NUMBER") "595-LP5907MFX-1.8NPB")
      )
      (libsource (lib "eagle-import") (part "LP5907-1.8V"))
    )
    (comp (ref "R1")
      (value "1k")
      (footprint "eagle-import:0207_10")
      (fields
        (field (name "MANUFACTURER_PART_NUMBER") "LR1F1K0")
        (field (name "MOUSER_PART_NUMBER") "279-LR1F1K0")
      )
      (libsource (lib "eagle-import") (part "LR1F1K0"))
    )
    (comp (ref "R2")
      (value "1k")
      (footprint "eagle-import:0207_10")
      (fields
        (field (name "MANUFACTURER_PART_NUMBER") "LR1F1K0")
        (field (name "MOUSER_PART_NUMBER") "279-LR1F1K0")
      )
      (libsource (lib "eagle-import") (part "LR1F1K0"))
    )
    (comp (ref "R2P")
      (value "220")
      (footprint "eagle-import:0411_15")
      (libsource (lib "eagle-import") (part "R-US_0411/15"))
    )
    (comp (ref "R2P1")
      (value "220")
      (footprint "eagle-import:0411_15")
      (libsource (lib "eagle-import") (part "R-US_0411/15"))
    )
    (comp (ref "R3")
      (value "1k")
      (footprint "eagle-import:0207_10")
      (fields
        (field (name "MANUFACTURER_PART_NUMBER") "LR1F1K0")
        (field (name "MOUSER_PART_NUMBER") "279-LR1F1K0")
      )
      (libsource (lib "eagle-import") (part "LR1F1K0"))
    )
    (comp (ref "R3O")
      (value "1M*")
      (footprint "eagle-import:0207_10")
      (fields
        (field (name "MANUFACTURER_PART_NUMBER") "LR1F1M0")
        (field (name "MOUSER_PART_NUMBER") "279-LR1F1M0")
      )
      (libsource (lib "eagle-import") (part "LR1F1M0"))
    )
    (comp (ref "R3O1")
      (value "1M*")
      (footprint "eagle-import:0207_10")
      (fields
        (field (name "MANUFACTURER_PART_NUMBER") "LR1F1M0")
        (field (name "MOUSER_PART_NUMBER") "279-LR1F1M0")
      )
      (libsource (lib "eagle-import") (part "LR1F1M0"))
    )
    (comp (ref "R3P")
      (value "220")
      (footprint "eagle-import:0411_15")
      (libsource (lib "eagle-import") (part "R-US_0411/15"))
    )
    (comp (ref "R3P1")
      (value "220")
      (footprint "eagle-import:0411_15")
      (libsource (lib "eagle-import") (part "R-US_0411/15"))
    )
    (comp (ref "R4")
      (value "1k")
      (footprint "eagle-import:0207_10")
      (fields
        (field (name "MANUFACTURER_PART_NUMBER") "LR1F1K0")
        (field (name "MOUSER_PART_NUMBER") "279-LR1F1K0")
      )
      (libsource (lib "eagle-import") (part "LR1F1K0"))
    )
    (comp (ref "R4P")
      (value "300k")
      (footprint "eagle-import:0411_15")
      (libsource (lib "eagle-import") (part "R-US_0411/15"))
    )
    (comp (ref "R4P1")
      (value "300k")
      (footprint "eagle-import:0411_15")
      (libsource (lib "eagle-import") (part "R-US_0411/15"))
    )
    (comp (ref "R5")
      (value "15k")
      (footprint "eagle-import:0411_15")
      (fields
        (field (name "MANUFACTURER_PART_NUMBER") "CPF215K000FKE14")
        (field (name "MOUSER_PART_NUMBER") "71-CPF2-F-15K-E3")
      )
      (libsource (lib "eagle-import") (part "CPF215K000FKE14"))
    )
    (comp (ref "R5P")
      (value "100k")
      (footprint "eagle-import:0411_15")
      (libsource (lib "eagle-import") (part "R-US_0411/15"))
    )
    (comp (ref "R5P1")
      (value "100k")
      (footprint "eagle-import:0411_15")
      (libsource (lib "eagle-import") (part "R-US_0411/15"))
    )
    (comp (ref "R6A")
      (value "1k")
      (footprint "eagle-import:RESC2012X60N")
      (fields
        (field (name "MANUFACTURER_PART_NUMBER") "CHP0805-FX-1001ELF")
        (field (name "MOUSER_PART_NUMBER") "652-CHP0805FX1001ELF")
      )
      (libsource (lib "eagle-import") (part "CHP0805-FX-1001ELF"))
    )
    (comp (ref "R6B")
      (value "1k")
      (footprint "eagle-import:RESC2012X60N")
      (fields
        (field (name "MANUFACTURER_PART_NUMBER") "CHP0805-FX-1001ELF")
        (field (name "MOUSER_PART_NUMBER") "652-CHP0805FX1001ELF")
      )
      (libsource (lib "eagle-import") (part "CHP0805-FX-1001ELF"))
    )
    (comp (ref "R6B2")
      (value "1k")
      (footprint "eagle-import:RESC2012X60N")
      (fields
        (field (name "MANUFACTURER_PART_NUMBER") "CHP0805-FX-1001ELF")
        (field (name "MOUSER_PART_NUMBER") "652-CHP0805FX1001ELF")
      )
      (libsource (lib "eagle-import") (part "CHP0805-FX-1001ELF"))
    )
    (comp (ref "R6B4")
      (value "1k")
      (footprint "eagle-import:RESC2012X60N")
      (fields
        (field (name "MANUFACTURER_PART_NUMBER") "CHP0805-FX-1001ELF")
        (field (name "MOUSER_PART_NUMBER") "652-CHP0805FX1001ELF")
      )
      (libsource (lib "eagle-import") (part "CHP0805-FX-1001ELF"))
    )
    (comp (ref "R6B6")
      (value "1k")
      (footprint "eagle-import:RESC2012X60N")
      (fields
        (field (name "MANUFACTURER_PART_NUMBER") "CHP0805-FX-1001ELF")
        (field (name "MOUSER_PART_NUMBER") "652-CHP0805FX1001ELF")
      )
      (libsource (lib "eagle-import") (part "CHP0805-FX-1001ELF"))
    )
    (comp (ref "R6D")
      (value "1k")
      (footprint "eagle-import:RESC2012X60N")
      (fields
        (field (name "MANUFACTURER_PART_NUMBER") "CHP0805-FX-1001ELF")
        (field (name "MOUSER_PART_NUMBER") "652-CHP0805FX1001ELF")
      )
      (libsource (lib "eagle-import") (part "CHP0805-FX-1001ELF"))
    )
    (comp (ref "R6P")
      (value "330")
      (footprint "eagle-import:0411_15")
      (libsource (lib "eagle-import") (part "R-US_0411/15"))
    )
    (comp (ref "R6P1")
      (value "330")
      (footprint "eagle-import:0411_15")
      (libsource (lib "eagle-import") (part "R-US_0411/15"))
    )
    (comp (ref "R6P2")
      (value "330")
      (footprint "eagle-import:0411_15")
      (libsource (lib "eagle-import") (part "R-US_0411/15"))
    )
    (comp (ref "R6P3")
      (value "330")
      (footprint "eagle-import:0411_15")
      (libsource (lib "eagle-import") (part "R-US_0411/15"))
    )
    (comp (ref "R7")
      (value "1k")
      (footprint "eagle-import:0207_10")
      (fields
        (field (name "MANUFACTURER_PART_NUMBER") "LR1F1K0")
        (field (name "MOUSER_PART_NUMBER") "279-LR1F1K0")
      )
      (libsource (lib "eagle-import") (part "LR1F1K0"))
    )
    (comp (ref "R7A")
      (value "33k")
      (footprint "eagle-import:R0805")
      (fields
        (field (name "MANUFACTURER_PART_NUMBER") "CPF0805B51KE1")
        (field (name "MOUSER_PART_NUMBER") "279-CPF0805B51KE1")
      )
      (libsource (lib "eagle-import") (part "CPF0805B51KE1"))
    )
    (comp (ref "R7B")
      (value "33k")
      (footprint "eagle-import:R0805")
      (fields
        (field (name "MANUFACTURER_PART_NUMBER") "CPF0805B51KE1")
        (field (name "MOUSER_PART_NUMBER") "279-CPF0805B51KE1")
      )
      (libsource (lib "eagle-import") (part "CPF0805B51KE1"))
    )
    (comp (ref "R7B2")
      (value "33k")
      (footprint "eagle-import:R0805")
      (fields
        (field (name "MANUFACTURER_PART_NUMBER") "CPF0805B51KE1")
        (field (name "MOUSER_PART_NUMBER") "279-CPF0805B51KE1")
      )
      (libsource (lib "eagle-import") (part "CPF0805B51KE1"))
    )
    (comp (ref "R7B4")
      (value "33k")
      (footprint "eagle-import:R0805")
      (fields
        (field (name "MANUFACTURER_PART_NUMBER") "CPF0805B51KE1")
        (field (name "MOUSER_PART_NUMBER") "279-CPF0805B51KE1")
      )
      (libsource (lib "eagle-import") (part "CPF0805B51KE1"))
    )
    (comp (ref "R7B6")
      (value "33k")
      (footprint "eagle-import:R0805")
      (fields
        (field (name "MANUFACTURER_PART_NUMBER") "CPF0805B51KE1")
        (field (name "MOUSER_PART_NUMBER") "279-CPF0805B51KE1")
      )
      (libsource (lib "eagle-import") (part "CPF0805B51KE1"))
    )
    (comp (ref "R7D")
      (value "33k")
      (footprint "eagle-import:R0805")
      (fields
        (field (name "MANUFACTURER_PART_NUMBER") "CPF0805B51KE1")
        (field (name "MOUSER_PART_NUMBER") "279-CPF0805B51KE1")
      )
      (libsource (lib "eagle-import") (part "CPF0805B51KE1"))
    )
    (comp (ref "R8")
      (value "1k")
      (footprint "eagle-import:0207_10")
      (fields
        (field (name "MANUFACTURER_PART_NUMBER") "LR1F1K0")
        (field (name "MOUSER_PART_NUMBER") "279-LR1F1K0")
      )
      (libsource (lib "eagle-import") (part "LR1F1K0"))
    )
    (comp (ref "R8A")
      (value "200k")
      (footprint "eagle-import:R0805")
      (fields
        (field (name "MANUFACTURER_PART_NUMBER") "RR1220P-204-D")
        (field (name "MOUSER_PART_NUMBER") "754-RR1220P-204D")
      )
      (libsource (lib "eagle-import") (part "RR1220P-204-D"))
    )
    (comp (ref "R8B")
      (value "200k")
      (footprint "eagle-import:R0805")
      (fields
        (field (name "MANUFACTURER_PART_NUMBER") "RR1220P-204-D")
        (field (name "MOUSER_PART_NUMBER") "754-RR1220P-204D")
      )
      (libsource (lib "eagle-import") (part "RR1220P-204-D"))
    )
    (comp (ref "R8B2")
      (value "200k")
      (footprint "eagle-import:R0805")
      (fields
        (field (name "MANUFACTURER_PART_NUMBER") "RR1220P-204-D")
        (field (name "MOUSER_PART_NUMBER") "754-RR1220P-204D")
      )
      (libsource (lib "eagle-import") (part "RR1220P-204-D"))
    )
    (comp (ref "R8B4")
      (value "200k")
      (footprint "eagle-import:R0805")
      (fields
        (field (name "MANUFACTURER_PART_NUMBER") "RR1220P-204-D")
        (field (name "MOUSER_PART_NUMBER") "754-RR1220P-204D")
      )
      (libsource (lib "eagle-import") (part "RR1220P-204-D"))
    )
    (comp (ref "R8B6")
      (value "200k")
      (footprint "eagle-import:R0805")
      (fields
        (field (name "MANUFACTURER_PART_NUMBER") "RR1220P-204-D")
        (field (name "MOUSER_PART_NUMBER") "754-RR1220P-204D")
      )
      (libsource (lib "eagle-import") (part "RR1220P-204-D"))
    )
    (comp (ref "R8D")
      (value "200k")
      (footprint "eagle-import:R0805")
      (fields
        (field (name "MANUFACTURER_PART_NUMBER") "RR1220P-204-D")
        (field (name "MOUSER_PART_NUMBER") "754-RR1220P-204D")
      )
      (libsource (lib "eagle-import") (part "RR1220P-204-D"))
    )
    (comp (ref "R9")
      (value "249")
      (footprint "eagle-import:0207_10")
      (fields (field (name "MANUFACTURER_PART_NUMBER") "MBB02070C2490FRP00"))
      (libsource (lib "eagle-import") (part "MBB02070C2490FRP00"))
    )
    (comp (ref "R10")
      (value "76.8")
      (footprint "eagle-import:0207_10")
      (fields (field (name "MANUFACTURER_PART_NUMBER") "YR1B76R8CC"))
      (libsource (lib "eagle-import") (part "YR1B76R8CC"))
    )
    (comp (ref "R11")
      (value "15k")
      (footprint "eagle-import:0411_15")
      (fields
        (field (name "MANUFACTURER_PART_NUMBER") "CPF215K000FKE14")
        (field (name "MOUSER_PART_NUMBER") "71-CPF2-F-15K-E3")
      )
      (libsource (lib "eagle-import") (part "CPF215K000FKE14"))
    )
    (comp (ref "R11O")
      (value "10k")
      (footprint "eagle-import:0207_10")
      (fields
        (field (name "MANUFACTURER_PART_NUMBER") "LR1F10K")
        (field (name "MOUSER_PART_NUMBER") "279-LR1F10K")
      )
      (libsource (lib "eagle-import") (part "LR1F10K"))
    )
    (comp (ref "R12O")
      (value "182")
      (footprint "eagle-import:0207_10")
      (fields
        (field (name "MANUFACTURER") "Yageo")
        (field (name "MANUFACTURER_PART_NUMBER") "MF0207FTE52-182R")
        (field (name "MOUSER_PART_NUMBER") "603-MF0207FTE52-182R")
      )
      (libsource (lib "eagle-import") (part "MF0207FTE52-182R"))
    )
    (comp (ref "R13")
      (value "1k")
      (footprint "eagle-import:0207_10")
      (fields
        (field (name "MANUFACTURER_PART_NUMBER") "LR1F1K0")
        (field (name "MOUSER_PART_NUMBER") "279-LR1F1K0")
      )
      (libsource (lib "eagle-import") (part "LR1F1K0"))
    )
    (comp (ref "R14")
      (value "1k")
      (footprint "eagle-import:0207_10")
      (fields
        (field (name "MANUFACTURER_PART_NUMBER") "LR1F1K0")
        (field (name "MOUSER_PART_NUMBER") "279-LR1F1K0")
      )
      (libsource (lib "eagle-import") (part "LR1F1K0"))
    )
    (comp (ref "R14O")
      (value "182")
      (footprint "eagle-import:0207_10")
      (fields
        (field (name "MANUFACTURER") "Yageo")
        (field (name "MANUFACTURER_PART_NUMBER") "MF0207FTE52-182R")
        (field (name "MOUSER_PART_NUMBER") "603-MF0207FTE52-182R")
      )
      (libsource (lib "eagle-import") (part "MF0207FTE52-182R"))
    )
    (comp (ref "R15")
      (value "249")
      (footprint "eagle-import:0207_10")
      (fields (field (name "MANUFACTURER_PART_NUMBER") "MBB02070C2490FRP00"))
      (libsource (lib "eagle-import") (part "MBB02070C2490FRP00"))
    )
    (comp (ref "R16")
      (value "76.8")
      (footprint "eagle-import:0207_10")
      (fields (field (name "MANUFACTURER_PART_NUMBER") "YR1B76R8CC"))
      (libsource (lib "eagle-import") (part "YR1B76R8CC"))
    )
    (comp (ref "R16O")
      (value "182")
      (footprint "eagle-import:0207_10")
      (fields
        (field (name "MANUFACTURER") "Yageo")
        (field (name "MANUFACTURER_PART_NUMBER") "MF0207FTE52-182R")
        (field (name "MOUSER_PART_NUMBER") "603-MF0207FTE52-182R")
      )
      (libsource (lib "eagle-import") (part "MF0207FTE52-182R"))
    )
    (comp (ref "R17")
      (value "402")
      (footprint "eagle-import:0617_22")
      (fields (field (name "MANUFACTURER_PART_NUMBER") "RWR80S4020FRB12"))
      (libsource (lib "eagle-import") (part "RWR80S4020FRB12"))
    )
    (comp (ref "R18")
      (value "402")
      (footprint "eagle-import:0617_22")
      (fields (field (name "MANUFACTURER_PART_NUMBER") "RWR80S4020FRB12"))
      (libsource (lib "eagle-import") (part "RWR80S4020FRB12"))
    )
    (comp (ref "R18O")
      (value "182")
      (footprint "eagle-import:0207_10")
      (fields
        (field (name "MANUFACTURER") "Yageo")
        (field (name "MANUFACTURER_PART_NUMBER") "MF0207FTE52-182R")
        (field (name "MOUSER_PART_NUMBER") "603-MF0207FTE52-182R")
      )
      (libsource (lib "eagle-import") (part "MF0207FTE52-182R"))
    )
    (comp (ref "R19")
      (value "15k")
      (footprint "eagle-import:0411_15")
      (fields
        (field (name "MANUFACTURER_PART_NUMBER") "CPF215K000FKE14")
        (field (name "MOUSER_PART_NUMBER") "71-CPF2-F-15K-E3")
      )
      (libsource (lib "eagle-import") (part "CPF215K000FKE14"))
    )
    (comp (ref "R19O")
      (value "10k")
      (footprint "eagle-import:0207_10")
      (fields
        (field (name "MANUFACTURER_PART_NUMBER") "LR1F10K")
        (field (name "MOUSER_PART_NUMBER") "279-LR1F10K")
      )
      (libsource (lib "eagle-import") (part "LR1F10K"))
    )
    (comp (ref "R20")
      (value "15k")
      (footprint "eagle-import:0411_15")
      (fields
        (field (name "MANUFACTURER_PART_NUMBER") "CPF215K000FKE14")
        (field (name "MOUSER_PART_NUMBER") "71-CPF2-F-15K-E3")
      )
      (libsource (lib "eagle-import") (part "CPF215K000FKE14"))
    )
    (comp (ref "R20O")
      (value "10k")
      (footprint "eagle-import:0207_10")
      (fields
        (field (name "MANUFACTURER_PART_NUMBER") "LR1F10K")
        (field (name "MOUSER_PART_NUMBER") "279-LR1F10K")
      )
      (libsource (lib "eagle-import") (part "LR1F10K"))
    )
    (comp (ref "R20O1")
      (value "10k")
      (footprint "eagle-import:0207_10")
      (fields
        (field (name "MANUFACTURER_PART_NUMBER") "LR1F10K")
        (field (name "MOUSER_PART_NUMBER") "279-LR1F10K")
      )
      (libsource (lib "eagle-import") (part "LR1F10K"))
    )
    (comp (ref "R20O2")
      (value "10k")
      (footprint "eagle-import:0207_10")
      (fields
        (field (name "MANUFACTURER_PART_NUMBER") "LR1F10K")
        (field (name "MOUSER_PART_NUMBER") "279-LR1F10K")
      )
      (libsource (lib "eagle-import") (part "LR1F10K"))
    )
    (comp (ref "R21O")
      (value "10k")
      (footprint "eagle-import:0207_10")
      (fields
        (field (name "MANUFACTURER_PART_NUMBER") "LR1F10K")
        (field (name "MOUSER_PART_NUMBER") "279-LR1F10K")
      )
      (libsource (lib "eagle-import") (part "LR1F10K"))
    )
    (comp (ref "R22O")
      (value "10k")
      (footprint "eagle-import:0207_10")
      (fields
        (field (name "MANUFACTURER_PART_NUMBER") "LR1F10K")
        (field (name "MOUSER_PART_NUMBER") "279-LR1F10K")
      )
      (libsource (lib "eagle-import") (part "LR1F10K"))
    )
    (comp (ref "R23O")
      (value "182")
      (footprint "eagle-import:0207_10")
      (fields
        (field (name "MANUFACTURER") "Yageo")
        (field (name "MANUFACTURER_PART_NUMBER") "MF0207FTE52-182R")
        (field (name "MOUSER_PART_NUMBER") "603-MF0207FTE52-182R")
      )
      (libsource (lib "eagle-import") (part "MF0207FTE52-182R"))
    )
    (comp (ref "R24O")
      (value "182")
      (footprint "eagle-import:0207_10")
      (fields
        (field (name "MANUFACTURER") "Yageo")
        (field (name "MANUFACTURER_PART_NUMBER") "MF0207FTE52-182R")
        (field (name "MOUSER_PART_NUMBER") "603-MF0207FTE52-182R")
      )
      (libsource (lib "eagle-import") (part "MF0207FTE52-182R"))
    )
    (comp (ref "R25O")
      (value "182")
      (footprint "eagle-import:0207_10")
      (fields
        (field (name "MANUFACTURER") "Yageo")
        (field (name "MANUFACTURER_PART_NUMBER") "MF0207FTE52-182R")
        (field (name "MOUSER_PART_NUMBER") "603-MF0207FTE52-182R")
      )
      (libsource (lib "eagle-import") (part "MF0207FTE52-182R"))
    )
    (comp (ref "R26O")
      (value "182")
      (footprint "eagle-import:0207_10")
      (fields
        (field (name "MANUFACTURER") "Yageo")
        (field (name "MANUFACTURER_PART_NUMBER") "MF0207FTE52-182R")
        (field (name "MOUSER_PART_NUMBER") "603-MF0207FTE52-182R")
      )
      (libsource (lib "eagle-import") (part "MF0207FTE52-182R"))
    )
    (comp (ref "R28O")
      (value "10k")
      (footprint "eagle-import:0207_10")
      (fields
        (field (name "MANUFACTURER_PART_NUMBER") "LR1F10K")
        (field (name "MOUSER_PART_NUMBER") "279-LR1F10K")
      )
      (libsource (lib "eagle-import") (part "LR1F10K"))
    )
    (comp (ref "R29O")
      (value "10k")
      (footprint "eagle-import:0207_10")
      (fields
        (field (name "MANUFACTURER_PART_NUMBER") "LR1F10K")
        (field (name "MOUSER_PART_NUMBER") "279-LR1F10K")
      )
      (libsource (lib "eagle-import") (part "LR1F10K"))
    )
    (comp (ref "R30O")
      (value "10k")
      (footprint "eagle-import:0207_10")
      (fields
        (field (name "MANUFACTURER_PART_NUMBER") "LR1F10K")
        (field (name "MOUSER_PART_NUMBER") "279-LR1F10K")
      )
      (libsource (lib "eagle-import") (part "LR1F10K"))
    )
    (comp (ref "SH1")
      (value "SHORTA5")
      (footprint "eagle-import:SHORT_ALL-50")
      (libsource (lib "eagle-import") (part "SHORTA5"))
    )
    (comp (ref "SH2")
      (value "SHORTA5")
      (footprint "eagle-import:SHORT_ALL-50")
      (libsource (lib "eagle-import") (part "SHORTA5"))
    )
    (comp (ref "SX1")
      (value "VT9-PT")
      (footprint "eagle-import:VT9-PT")
      (libsource (lib "eagle-import") (part "VT9-PT"))
    )
    (comp (ref "SX2")
      (value "VT9-PT")
      (footprint "eagle-import:VT9-PT")
      (libsource (lib "eagle-import") (part "VT9-PT"))
    )
    (comp (ref "SX3")
      (value "VT9-PT")
      (footprint "eagle-import:VT9-PT")
      (libsource (lib "eagle-import") (part "VT9-PT"))
    )
    (comp (ref "SX4")
      (value "VT9-PT")
      (footprint "eagle-import:VT9-PT")
      (libsource (lib "eagle-import") (part "VT9-PT"))
    )
    (comp (ref "U1")
      (value "LM317MTG")
      (footprint "eagle-import:TO254P482X997X2018-3P")
      (fields (field (name "MOUSER_PART_NUMBER") "863-LM317MTG"))
      (libsource (lib "eagle-import") (part "LM317MTG"))
    )
    (comp (ref "U2")
      (value "LM317MTG")
      (footprint "eagle-import:TO254P482X997X2018-3P")
      (fields (field (name "MOUSER_PART_NUMBER") "863-LM317MTG"))
      (libsource (lib "eagle-import") (part "LM317MTG"))
    )
    (comp (ref "Z1")
      (value "BZX79-C16,113")
      (footprint "eagle-import:DIOAD1165W56L425D185")
      (libsource (lib "eagle-import") (part "BZX79-C16,113"))
    )
    (comp (ref "Z2")
      (value "BZX79-C16,113")
      (footprint "eagle-import:DIOAD1165W56L425D185")
      (libsource (lib "eagle-import") (part "BZX79-C16,113"))
    )
    (comp (ref "Z3")
      (value "1N750")
      (footprint "eagle-import:DIOAD1256W56L444D203")
      (fields (field (name "MOUSER_PART_NUMBER") "494-1N750(DO-35)"))
      (libsource (lib "eagle-import") (part "1N750"))
    )
    (comp (ref "Z4")
      (value "1N750")
      (footprint "eagle-import:DIOAD1256W56L444D203")
      (fields (field (name "MOUSER_PART_NUMBER") "494-1N750(DO-35)"))
      (libsource (lib "eagle-import") (part "1N750"))
    )
    (comp (ref "Z5")
      (value "BZX79-C16,113")
      (footprint "eagle-import:DIOAD1165W56L425D185")
      (libsource (lib "eagle-import") (part "BZX79-C16,113"))
    )
    (comp (ref "Z6")
      (value "BZX79-C16,113")
      (footprint "eagle-import:DIOAD1165W56L425D185")
      (libsource (lib "eagle-import") (part "BZX79-C16,113"))
    )
  )
  (nets
    (net (code "1") (name "+1V8{slash}1") (class "Default")
      (node (ref "C27A1") (pin "1") (pinfunction "1_1") (pintype "passive"))
      (node (ref "C28A1") (pin "1") (pinfunction "1_1") (pintype "passive"))
      (node (ref "J9") (pin "6") (pinfunction "6_6") (pintype "bidirectional"))
      (node (ref "LDO1") (pin "5") (pinfunction "VOUT_5") (pintype "bidirectional"))
    )
    (net (code "2") (name "+1V8{slash}2") (class "Default")
      (node (ref "C27A") (pin "1") (pinfunction "1_1") (pintype "passive"))
      (node (ref "C28A") (pin "1") (pinfunction "1_1") (pintype "passive"))
      (node (ref "J7") (pin "1") (pinfunction "1_1") (pintype "bidirectional"))
      (node (ref "LDO7") (pin "5") (pinfunction "VOUT_5") (pintype "bidirectional"))
    )
    (net (code "3") (name "+3V3{slash}1") (class "Default")
      (node (ref "C18B6") (pin "1") (pinfunction "1_1") (pintype "passive"))
      (node (ref "C26A1") (pin "1") (pinfunction "1_1") (pintype "passive"))
      (node (ref "IC10") (pin "10") (pinfunction "OUT_10") (pintype "bidirectional"))
      (node (ref "IC10") (pin "9") (pinfunction "OUTS_9") (pintype "bidirectional"))
      (node (ref "J12") (pin "6") (pinfunction "6_6") (pintype "bidirectional"))
      (node (ref "J9") (pin "4") (pinfunction "4_4") (pintype "bidirectional"))
      (node (ref "LDO1") (pin "1") (pinfunction "VIN_1") (pintype "bidirectional"))
      (node (ref "LDO1") (pin "3") (pinfunction "EN_3") (pintype "bidirectional"))
    )
    (net (code "4") (name "+3V3{slash}2") (class "Default")
      (node (ref "C18A") (pin "1") (pinfunction "1_1") (pintype "passive"))
      (node (ref "C26A") (pin "1") (pinfunction "1_1") (pintype "passive"))
      (node (ref "IC2") (pin "10") (pinfunction "OUT_10") (pintype "bidirectional"))
      (node (ref "IC2") (pin "9") (pinfunction "OUTS_9") (pintype "bidirectional"))
      (node (ref "J5") (pin "6") (pinfunction "6_6") (pintype "bidirectional"))
      (node (ref "J7") (pin "3") (pinfunction "3_3") (pintype "bidirectional"))
      (node (ref "LDO7") (pin "1") (pinfunction "VIN_1") (pintype "bidirectional"))
      (node (ref "LDO7") (pin "3") (pinfunction "EN_3") (pintype "bidirectional"))
    )
    (net (code "5") (name "+5V{slash}L{slash}1") (class "Default")
      (node (ref "C18D") (pin "1") (pinfunction "1_1") (pintype "passive"))
      (node (ref "IC1") (pin "10") (pinfunction "OUT_10") (pintype "bidirectional"))
      (node (ref "IC1") (pin "9") (pinfunction "OUTS_9") (pintype "bidirectional"))
      (node (ref "J1") (pin "6") (pinfunction "6_6") (pintype "bidirectional"))
      (node (ref "J7") (pin "4") (pinfunction "4_4") (pintype "bidirectional"))
    )
    (net (code "6") (name "+5V{slash}L{slash}2") (class "Default")
      (node (ref "C18B") (pin "1") (pinfunction "1_1") (pintype "passive"))
      (node (ref "IC5") (pin "10") (pinfunction "OUT_10") (pintype "bidirectional"))
      (node (ref "IC5") (pin "9") (pinfunction "OUTS_9") (pintype "bidirectional"))
      (node (ref "J17") (pin "6") (pinfunction "6_6") (pintype "bidirectional"))
      (node (ref "J7") (pin "5") (pinfunction "5_5") (pintype "bidirectional"))
    )
    (net (code "7") (name "+5V{slash}L{slash}3") (class "Default")
      (node (ref "C20A") (pin "1") (pinfunction "1_1") (pintype "passive"))
      (node (ref "C21A") (pin "1") (pinfunction "1_1") (pintype "passive"))
      (node (ref "IC2") (pin "1") (pinfunction "IN_1") (pintype "bidirectional"))
      (node (ref "IC2") (pin "2") (pinfunction "IN_2") (pintype "bidirectional"))
      (node (ref "IC2") (pin "3") (pinfunction "EN/UV_3") (pintype "bidirectional"))
      (node (ref "IC3") (pin "2") (pinfunction "OUT_2") (pintype "passive"))
      (node (ref "IC3") (pin "4") (pinfunction "OUT_4") (pintype "passive"))
      (node (ref "J5") (pin "7") (pinfunction "7_7") (pintype "bidirectional"))
      (node (ref "J5") (pin "8") (pinfunction "8_8") (pintype "bidirectional"))
      (node (ref "J7") (pin "2") (pinfunction "2_2") (pintype "bidirectional"))
      (node (ref "R8A") (pin "1") (pinfunction "1_1") (pintype "passive"))
    )
    (net (code "8") (name "+5V{slash}R{slash}1") (class "Default")
      (node (ref "C18B4") (pin "1") (pinfunction "1_1") (pintype "passive"))
      (node (ref "IC8") (pin "10") (pinfunction "OUT_10") (pintype "bidirectional"))
      (node (ref "IC8") (pin "9") (pinfunction "OUTS_9") (pintype "bidirectional"))
      (node (ref "J10") (pin "6") (pinfunction "6_6") (pintype "bidirectional"))
      (node (ref "J9") (pin "3") (pinfunction "3_3") (pintype "bidirectional"))
    )
    (net (code "9") (name "+5V{slash}R{slash}2") (class "Default")
      (node (ref "C18B2") (pin "1") (pinfunction "1_1") (pintype "passive"))
      (node (ref "IC6") (pin "10") (pinfunction "OUT_10") (pintype "bidirectional"))
      (node (ref "IC6") (pin "9") (pinfunction "OUTS_9") (pintype "bidirectional"))
      (node (ref "J8") (pin "6") (pinfunction "6_6") (pintype "bidirectional"))
      (node (ref "J9") (pin "2") (pinfunction "2_2") (pintype "bidirectional"))
    )
    (net (code "10") (name "+5V{slash}R{slash}3") (class "Default")
      (node (ref "IC4") (pin "2") (pinfunction "OUT_2") (pintype "passive"))
      (node (ref "IC4") (pin "4") (pinfunction "OUT_4") (pintype "passive"))
      (node (ref "J9") (pin "5") (pinfunction "5_5") (pintype "bidirectional"))
    )
    (net (code "11") (name "+240VDC{slash}1") (class "Default")
      (node (ref "C1") (pin "1") (pinfunction "1_1") (pintype "passive"))
      (node (ref "C3") (pin "1") (pinfunction "1_1") (pintype "passive"))
      (node (ref "C3P2") (pin "1") (pinfunction "+_1") (pintype "bidirectional"))
      (node (ref "C5P2") (pin "1") (pinfunction "+_1") (pintype "bidirectional"))
      (node (ref "C6P2") (pin "1") (pinfunction "+_1") (pintype "bidirectional"))
      (node (ref "C7P2") (pin "1") (pinfunction "+_1") (pintype "bidirectional"))
      (node (ref "R17") (pin "1") (pinfunction "1_1") (pintype "passive"))
      (node (ref "R19") (pin "2") (pinfunction "2_2") (pintype "passive"))
      (node (ref "R4P1") (pin "2") (pinfunction "2_2") (pintype "passive"))
      (node (ref "R5") (pin "2") (pinfunction "2_2") (pintype "passive"))
      (node (ref "R6P2") (pin "1") (pinfunction "1_1") (pintype "passive"))
    )
    (net (code "12") (name "+240VDC{slash}2") (class "Default")
      (node (ref "C2") (pin "1") (pinfunction "1_1") (pintype "passive"))
      (node (ref "C3P") (pin "1") (pinfunction "+_1") (pintype "bidirectional"))
      (node (ref "C4") (pin "1") (pinfunction "1_1") (pintype "passive"))
      (node (ref "C5P") (pin "1") (pinfunction "+_1") (pintype "bidirectional"))
      (node (ref "C6P") (pin "1") (pinfunction "+_1") (pintype "bidirectional"))
      (node (ref "C7P") (pin "1") (pinfunction "+_1") (pintype "bidirectional"))
      (node (ref "R11") (pin "2") (pinfunction "2_2") (pintype "passive"))
      (node (ref "R18") (pin "2") (pinfunction "2_2") (pintype "passive"))
      (node (ref "R20") (pin "1") (pinfunction "1_1") (pintype "passive"))
      (node (ref "R4P") (pin "2") (pinfunction "2_2") (pintype "passive"))
      (node (ref "R6P") (pin "1") (pinfunction "1_1") (pintype "passive"))
    )
    (net (code "13") (name "6.3_VAC_BLU{slash}1") (class "Default")
      (node (ref "D19") (pin "1") (pinfunction "K_1") (pintype "bidirectional"))
      (node (ref "D22") (pin "2") (pinfunction "A_2") (pintype "bidirectional"))
      (node (ref "J4") (pin "4") (pinfunction "4_4") (pintype "bidirectional"))
    )
    (net (code "14") (name "6.3_VAC_BLU{slash}2") (class "Default")
      (node (ref "D11") (pin "1") (pinfunction "K_1") (pintype "bidirectional"))
      (node (ref "D14") (pin "2") (pinfunction "A_2") (pintype "bidirectional"))
      (node (ref "J6") (pin "8") (pinfunction "8_8") (pintype "bidirectional"))
    )
    (net (code "15") (name "6.3_VAC_GRN{slash}1") (class "Default")
      (node (ref "D20") (pin "1") (pinfunction "K_1") (pintype "bidirectional"))
      (node (ref "D21") (pin "2") (pinfunction "A_2") (pintype "bidirectional"))
      (node (ref "J4") (pin "3") (pinfunction "3_3") (pintype "bidirectional"))
    )
    (net (code "16") (name "6.3_VAC_GRN{slash}2") (class "Default")
      (node (ref "D12") (pin "1") (pinfunction "K_1") (pintype "bidirectional"))
      (node (ref "D13") (pin "2") (pinfunction "A_2") (pintype "bidirectional"))
      (node (ref "J6") (pin "9") (pinfunction "9_9") (pintype "bidirectional"))
    )
    (net (code "17") (name "66.3VAC{slash}BRN{slash}1") (class "Default")
      (node (ref "J4") (pin "5") (pinfunction "5_5") (pintype "bidirectional"))
      (node (ref "R3P1") (pin "1") (pinfunction "1_1") (pintype "passive"))
      (node (ref "SX1") (pin "4") (pinfunction "4_4") (pintype "passive"))
      (node (ref "SX3") (pin "4") (pinfunction "4_4") (pintype "passive"))
    )
    (net (code "18") (name "66.3VAC{slash}BRN{slash}2") (class "Default")
      (node (ref "J6") (pin "7") (pinfunction "7_7") (pintype "bidirectional"))
      (node (ref "R3P") (pin "1") (pinfunction "1_1") (pintype "passive"))
      (node (ref "SX2") (pin "4") (pinfunction "4_4") (pintype "passive"))
      (node (ref "SX4") (pin "4") (pinfunction "4_4") (pintype "passive"))
    )
    (net (code "19") (name "66.3VAC{slash}ORG{slash}1") (class "Default")
      (node (ref "J4") (pin "6") (pinfunction "6_6") (pintype "bidirectional"))
      (node (ref "R2P1") (pin "2") (pinfunction "2_2") (pintype "passive"))
      (node (ref "SX1") (pin "5") (pinfunction "5_5") (pintype "passive"))
      (node (ref "SX3") (pin "5") (pinfunction "5_5") (pintype "passive"))
    )
    (net (code "20") (name "66.3VAC{slash}ORG{slash}2") (class "Default")
      (node (ref "J6") (pin "6") (pinfunction "6_6") (pintype "bidirectional"))
      (node (ref "R2P") (pin "2") (pinfunction "2_2") (pintype "passive"))
      (node (ref "SX2") (pin "5") (pinfunction "5_5") (pintype "passive"))
      (node (ref "SX4") (pin "5") (pinfunction "5_5") (pintype "passive"))
    )
    (net (code "21") (name "115_VAC_BLK{slash}1") (class "Default")
      (node (ref "D15") (pin "1") (pinfunction "K_1") (pintype "bidirectional"))
      (node (ref "D18") (pin "2") (pinfunction "A_2") (pintype "bidirectional"))
      (node (ref "J4") (pin "10") (pinfunction "10_10") (pintype "bidirectional"))
    )
    (net (code "22") (name "115_VAC_BLK{slash}2") (class "Default")
      (node (ref "D10") (pin "2") (pinfunction "A_2") (pintype "bidirectional"))
      (node (ref "D7") (pin "1") (pinfunction "K_1") (pintype "bidirectional"))
      (node (ref "J6") (pin "2") (pinfunction "2_2") (pintype "bidirectional"))
    )
    (net (code "23") (name "115_VAC_RED{slash}1") (class "Default")
      (node (ref "D16") (pin "1") (pinfunction "K_1") (pintype "bidirectional"))
      (node (ref "D17") (pin "2") (pinfunction "A_2") (pintype "bidirectional"))
      (node (ref "J4") (pin "9") (pinfunction "9_9") (pintype "bidirectional"))
    )
    (net (code "24") (name "115_VAC_RED{slash}2") (class "Default")
      (node (ref "D8") (pin "1") (pinfunction "K_1") (pintype "bidirectional"))
      (node (ref "D9") (pin "2") (pinfunction "A_2") (pintype "bidirectional"))
      (node (ref "J6") (pin "3") (pinfunction "3_3") (pintype "bidirectional"))
    )
    (net (code "25") (name "AGND{slash}1") (class "Default")
      (node (ref "C1") (pin "2") (pinfunction "2_2") (pintype "passive"))
      (node (ref "C1P2") (pin "2") (pinfunction "-_2") (pintype "bidirectional"))
      (node (ref "C2P2") (pin "2") (pinfunction "-_2") (pintype "bidirectional"))
      (node (ref "C3") (pin "2") (pinfunction "2_2") (pintype "passive"))
      (node (ref "C3P2") (pin "2") (pinfunction "-_2") (pintype "bidirectional"))
      (node (ref "C4P1") (pin "2") (pinfunction "-_2") (pintype "bidirectional"))
      (node (ref "C5P2") (pin "2") (pinfunction "-_2") (pintype "bidirectional"))
      (node (ref "C6P2") (pin "2") (pinfunction "-_2") (pintype "bidirectional"))
      (node (ref "C7P2") (pin "2") (pinfunction "-_2") (pintype "bidirectional"))
      (node (ref "D15") (pin "2") (pinfunction "A_2") (pintype "bidirectional"))
      (node (ref "D16") (pin "2") (pinfunction "A_2") (pintype "bidirectional"))
      (node (ref "J13") (pin "2") (pinfunction "2_2") (pintype "passive"))
      (node (ref "J13") (pin "5") (pinfunction "5_5") (pintype "passive"))
      (node (ref "J3") (pin "1") (pinfunction "SLEEVE_1") (pintype "bidirectional"))
      (node (ref "R10") (pin "1") (pinfunction "1_1") (pintype "passive"))
      (node (ref "R11O") (pin "2") (pinfunction "2_2") (pintype "passive"))
      (node (ref "R19O") (pin "1") (pinfunction "1_1") (pintype "passive"))
      (node (ref "R20O") (pin "2") (pinfunction "2_2") (pintype "passive"))
      (node (ref "R20O1") (pin "1") (pinfunction "1_1") (pintype "passive"))
      (node (ref "R21O") (pin "1") (pinfunction "1_1") (pintype "passive"))
      (node (ref "R3O") (pin "2") (pinfunction "2_2") (pintype "passive"))
      (node (ref "R5P1") (pin "1") (pinfunction "1_1") (pintype "passive"))
      (node (ref "R9") (pin "1") (pinfunction "1_1") (pintype "passive"))
      (node (ref "SH1") (pin "2") (pinfunction "P$2_2") (pintype "bidirectional"))
      (node (ref "U1") (pin "1") (pinfunction "ADJ_1") (pintype "input"))
      (node (ref "Z1") (pin "1") (pinfunction "C_1") (pintype "passive"))
    )
    (net (code "26") (name "AGND{slash}2") (class "Default")
      (node (ref "C1P") (pin "2") (pinfunction "-_2") (pintype "bidirectional"))
      (node (ref "C2") (pin "2") (pinfunction "2_2") (pintype "passive"))
      (node (ref "C2P") (pin "2") (pinfunction "-_2") (pintype "bidirectional"))
      (node (ref "C3P") (pin "2") (pinfunction "-_2") (pintype "bidirectional"))
      (node (ref "C4") (pin "2") (pinfunction "2_2") (pintype "passive"))
      (node (ref "C4P") (pin "2") (pinfunction "-_2") (pintype "bidirectional"))
      (node (ref "C5P") (pin "2") (pinfunction "-_2") (pintype "bidirectional"))
      (node (ref "C6P") (pin "2") (pinfunction "-_2") (pintype "bidirectional"))
      (node (ref "C7P") (pin "2") (pinfunction "-_2") (pintype "bidirectional"))
      (node (ref "D7") (pin "2") (pinfunction "A_2") (pintype "bidirectional"))
      (node (ref "D8") (pin "2") (pinfunction "A_2") (pintype "bidirectional"))
      (node (ref "J2") (pin "2") (pinfunction "2_2") (pintype "passive"))
      (node (ref "J2") (pin "5") (pinfunction "5_5") (pintype "passive"))
      (node (ref "R15") (pin "1") (pinfunction "1_1") (pintype "passive"))
      (node (ref "R16") (pin "1") (pinfunction "1_1") (pintype "passive"))
      (node (ref "R20O2") (pin "1") (pinfunction "1_1") (pintype "passive"))
      (node (ref "R22O") (pin "2") (pinfunction "2_2") (pintype "passive"))
      (node (ref "R28O") (pin "1") (pinfunction "1_1") (pintype "passive"))
      (node (ref "R29O") (pin "2") (pinfunction "2_2") (pintype "passive"))
      (node (ref "R30O") (pin "1") (pinfunction "1_1") (pintype "passive"))
      (node (ref "R3O1") (pin "2") (pinfunction "2_2") (pintype "passive"))
      (node (ref "R5P") (pin "1") (pinfunction "1_1") (pintype "passive"))
      (node (ref "SH2") (pin "2") (pinfunction "P$2_2") (pintype "bidirectional"))
      (node (ref "U2") (pin "1") (pinfunction "ADJ_1") (pintype "input"))
      (node (ref "Z6") (pin "1") (pinfunction "C_1") (pintype "passive"))
    )
    (net (code "27") (name "DGND{slash}1") (class "Default")
      (node (ref "C18B2") (pin "2") (pinfunction "2_2") (pintype "passive"))
      (node (ref "C18B4") (pin "2") (pinfunction "2_2") (pintype "passive"))
      (node (ref "C18B6") (pin "2") (pinfunction "2_2") (pintype "passive"))
      (node (ref "C19B2") (pin "2") (pinfunction "2_2") (pintype "passive"))
      (node (ref "C19B2") (pin "DGND") (pinfunction "2_DGND") (pintype "passive"))
      (node (ref "C19B4") (pin "2") (pinfunction "2_2") (pintype "passive"))
      (node (ref "C19B4") (pin "DGND") (pinfunction "2_DGND") (pintype "passive"))
      (node (ref "C19B6") (pin "2") (pinfunction "2_2") (pintype "passive"))
      (node (ref "C19B6") (pin "DGND") (pinfunction "2_DGND") (pintype "passive"))
      (node (ref "C1P3") (pin "2") (pinfunction "-_2") (pintype "bidirectional"))
      (node (ref "C20B2") (pin "2") (pinfunction "2_2") (pintype "passive"))
      (node (ref "C20B4") (pin "2") (pinfunction "2_2") (pintype "passive"))
      (node (ref "C20B6") (pin "2") (pinfunction "2_2") (pintype "passive"))
      (node (ref "C21B2") (pin "2") (pinfunction "2_2") (pintype "passive"))
      (node (ref "C21B4") (pin "2") (pinfunction "2_2") (pintype "passive"))
      (node (ref "C21B6") (pin "2") (pinfunction "2_2") (pintype "passive"))
      (node (ref "C26A1") (pin "2") (pinfunction "2_2") (pintype "passive"))
      (node (ref "C27A1") (pin "2") (pinfunction "2_2") (pintype "passive"))
      (node (ref "C28A1") (pin "2") (pinfunction "2_2") (pintype "passive"))
      (node (ref "C2P3") (pin "2") (pinfunction "-_2") (pintype "bidirectional"))
      (node (ref "C3P3") (pin "2") (pinfunction "-_2") (pintype "bidirectional"))
      (node (ref "C5P3") (pin "2") (pinfunction "-_2") (pintype "bidirectional"))
      (node (ref "C6P3") (pin "2") (pinfunction "-_2") (pintype "bidirectional"))
      (node (ref "C7P3") (pin "2") (pinfunction "-_2") (pintype "bidirectional"))
      (node (ref "D19") (pin "2") (pinfunction "A_2") (pintype "bidirectional"))
      (node (ref "D20") (pin "2") (pinfunction "A_2") (pintype "bidirectional"))
      (node (ref "IC10") (pin "11") (pinfunction "GND_11") (pintype "bidirectional"))
      (node (ref "IC10") (pin "8") (pinfunction "GND_8") (pintype "bidirectional"))
      (node (ref "IC10") (pin "P$1") (pinfunction "GND_P$1") (pintype "bidirectional"))
      (node (ref "IC10") (pin "P$2") (pinfunction "GND_P$2") (pintype "bidirectional"))
      (node (ref "IC10") (pin "P$3") (pinfunction "GND_P$3") (pintype "bidirectional"))
      (node (ref "IC10") (pin "P$4") (pinfunction "GND_P$4") (pintype "bidirectional"))
      (node (ref "IC10") (pin "P$5") (pinfunction "GND_P$5") (pintype "bidirectional"))
      (node (ref "IC10") (pin "P$6") (pinfunction "GND_P$6") (pintype "bidirectional"))
      (node (ref "IC6") (pin "11") (pinfunction "GND_11") (pintype "bidirectional"))
      (node (ref "IC6") (pin "8") (pinfunction "GND_8") (pintype "bidirectional"))
      (node (ref "IC6") (pin "P$1") (pinfunction "GND_P$1") (pintype "bidirectional"))
      (node (ref "IC6") (pin "P$2") (pinfunction "GND_P$2") (pintype "bidirectional"))
      (node (ref "IC6") (pin "P$3") (pinfunction "GND_P$3") (pintype "bidirectional"))
      (node (ref "IC6") (pin "P$4") (pinfunction "GND_P$4") (pintype "bidirectional"))
      (node (ref "IC6") (pin "P$5") (pinfunction "GND_P$5") (pintype "bidirectional"))
      (node (ref "IC6") (pin "P$6") (pinfunction "GND_P$6") (pintype "bidirectional"))
      (node (ref "IC8") (pin "11") (pinfunction "GND_11") (pintype "bidirectional"))
      (node (ref "IC8") (pin "8") (pinfunction "GND_8") (pintype "bidirectional"))
      (node (ref "IC8") (pin "P$1") (pinfunction "GND_P$1") (pintype "bidirectional"))
      (node (ref "IC8") (pin "P$2") (pinfunction "GND_P$2") (pintype "bidirectional"))
      (node (ref "IC8") (pin "P$3") (pinfunction "GND_P$3") (pintype "bidirectional"))
      (node (ref "IC8") (pin "P$4") (pinfunction "GND_P$4") (pintype "bidirectional"))
      (node (ref "IC8") (pin "P$5") (pinfunction "GND_P$5") (pintype "bidirectional"))
      (node (ref "IC8") (pin "P$6") (pinfunction "GND_P$6") (pintype "bidirectional"))
      (node (ref "J10") (pin "5") (pinfunction "5_5") (pintype "bidirectional"))
      (node (ref "J12") (pin "5") (pinfunction "5_5") (pintype "bidirectional"))
      (node (ref "J8") (pin "5") (pinfunction "5_5") (pintype "bidirectional"))
      (node (ref "J9") (pin "1") (pinfunction "1_1") (pintype "bidirectional"))
      (node (ref "LDO1") (pin "2") (pinfunction "GND_2") (pintype "bidirectional"))
      (node (ref "LDO1") (pin "DGND") (pinfunction "GND_DGND") (pintype "bidirectional"))
      (node (ref "LDO1") (pin "DGND2") (pinfunction "GND_DGND2") (pintype "bidirectional"))
      (node (ref "LDO1") (pin "DGND3") (pinfunction "GND_DGND3") (pintype "bidirectional"))
      (node (ref "R6B2") (pin "2") (pinfunction "2_2") (pintype "passive"))
      (node (ref "R6B4") (pin "2") (pinfunction "2_2") (pintype "passive"))
      (node (ref "R6B6") (pin "2") (pinfunction "2_2") (pintype "passive"))
      (node (ref "R7B2") (pin "2") (pinfunction "2_2") (pintype "passive"))
      (node (ref "R7B4") (pin "2") (pinfunction "2_2") (pintype "passive"))
      (node (ref "R7B6") (pin "2") (pinfunction "2_2") (pintype "passive"))
      (node (ref "SH1") (pin "1") (pinfunction "P$1_1") (pintype "bidirectional"))
    )
    (net (code "28") (name "DGND{slash}2") (class "Default")
      (node (ref "C18A") (pin "2") (pinfunction "2_2") (pintype "passive"))
      (node (ref "C18B") (pin "2") (pinfunction "2_2") (pintype "passive"))
      (node (ref "C18D") (pin "2") (pinfunction "2_2") (pintype "passive"))
      (node (ref "C19A") (pin "2") (pinfunction "2_2") (pintype "passive"))
      (node (ref "C19A") (pin "DGND") (pinfunction "2_DGND") (pintype "passive"))
      (node (ref "C19B") (pin "2") (pinfunction "2_2") (pintype "passive"))
      (node (ref "C19B") (pin "DGND") (pinfunction "2_DGND") (pintype "passive"))
      (node (ref "C19D") (pin "2") (pinfunction "2_2") (pintype "passive"))
      (node (ref "C19D") (pin "DGND") (pinfunction "2_DGND") (pintype "passive"))
      (node (ref "C1P1") (pin "2") (pinfunction "-_2") (pintype "bidirectional"))
      (node (ref "C20A") (pin "2") (pinfunction "2_2") (pintype "passive"))
      (node (ref "C20B") (pin "2") (pinfunction "2_2") (pintype "passive"))
      (node (ref "C20D") (pin "2") (pinfunction "2_2") (pintype "passive"))
      (node (ref "C21A") (pin "2") (pinfunction "2_2") (pintype "passive"))
      (node (ref "C21B") (pin "2") (pinfunction "2_2") (pintype "passive"))
      (node (ref "C21D") (pin "2") (pinfunction "2_2") (pintype "passive"))
      (node (ref "C26A") (pin "2") (pinfunction "2_2") (pintype "passive"))
      (node (ref "C27A") (pin "2") (pinfunction "2_2") (pintype "passive"))
      (node (ref "C28A") (pin "2") (pinfunction "2_2") (pintype "passive"))
      (node (ref "C2P1") (pin "2") (pinfunction "-_2") (pintype "bidirectional"))
      (node (ref "C3P1") (pin "2") (pinfunction "-_2") (pintype "bidirectional"))
      (node (ref "C5P1") (pin "2") (pinfunction "-_2") (pintype "bidirectional"))
      (node (ref "C6P1") (pin "2") (pinfunction "-_2") (pintype "bidirectional"))
      (node (ref "C7P1") (pin "2") (pinfunction "-_2") (pintype "bidirectional"))
      (node (ref "D11") (pin "2") (pinfunction "A_2") (pintype "bidirectional"))
      (node (ref "D12") (pin "2") (pinfunction "A_2") (pintype "bidirectional"))
      (node (ref "IC1") (pin "11") (pinfunction "GND_11") (pintype "bidirectional"))
      (node (ref "IC1") (pin "8") (pinfunction "GND_8") (pintype "bidirectional"))
      (node (ref "IC1") (pin "P$1") (pinfunction "GND_P$1") (pintype "bidirectional"))
      (node (ref "IC1") (pin "P$2") (pinfunction "GND_P$2") (pintype "bidirectional"))
      (node (ref "IC1") (pin "P$3") (pinfunction "GND_P$3") (pintype "bidirectional"))
      (node (ref "IC1") (pin "P$4") (pinfunction "GND_P$4") (pintype "bidirectional"))
      (node (ref "IC1") (pin "P$5") (pinfunction "GND_P$5") (pintype "bidirectional"))
      (node (ref "IC1") (pin "P$6") (pinfunction "GND_P$6") (pintype "bidirectional"))
      (node (ref "IC2") (pin "11") (pinfunction "GND_11") (pintype "bidirectional"))
      (node (ref "IC2") (pin "8") (pinfunction "GND_8") (pintype "bidirectional"))
      (node (ref "IC2") (pin "P$1") (pinfunction "GND_P$1") (pintype "bidirectional"))
      (node (ref "IC2") (pin "P$2") (pinfunction "GND_P$2") (pintype "bidirectional"))
      (node (ref "IC2") (pin "P$3") (pinfunction "GND_P$3") (pintype "bidirectional"))
      (node (ref "IC2") (pin "P$4") (pinfunction "GND_P$4") (pintype "bidirectional"))
      (node (ref "IC2") (pin "P$5") (pinfunction "GND_P$5") (pintype "bidirectional"))
      (node (ref "IC2") (pin "P$6") (pinfunction "GND_P$6") (pintype "bidirectional"))
      (node (ref "IC5") (pin "11") (pinfunction "GND_11") (pintype "bidirectional"))
      (node (ref "IC5") (pin "8") (pinfunction "GND_8") (pintype "bidirectional"))
      (node (ref "IC5") (pin "P$1") (pinfunction "GND_P$1") (pintype "bidirectional"))
      (node (ref "IC5") (pin "P$2") (pinfunction "GND_P$2") (pintype "bidirectional"))
      (node (ref "IC5") (pin "P$3") (pinfunction "GND_P$3") (pintype "bidirectional"))
      (node (ref "IC5") (pin "P$4") (pinfunction "GND_P$4") (pintype "bidirectional"))
      (node (ref "IC5") (pin "P$5") (pinfunction "GND_P$5") (pintype "bidirectional"))
      (node (ref "IC5") (pin "P$6") (pinfunction "GND_P$6") (pintype "bidirectional"))
      (node (ref "J1") (pin "5") (pinfunction "5_5") (pintype "bidirectional"))
      (node (ref "J17") (pin "5") (pinfunction "5_5") (pintype "bidirectional"))
      (node (ref "J5") (pin "5") (pinfunction "5_5") (pintype "bidirectional"))
      (node (ref "J7") (pin "6") (pinfunction "6_6") (pintype "bidirectional"))
      (node (ref "LDO7") (pin "2") (pinfunction "GND_2") (pintype "bidirectional"))
      (node (ref "LDO7") (pin "DGND") (pinfunction "GND_DGND") (pintype "bidirectional"))
      (node (ref "LDO7") (pin "DGND2") (pinfunction "GND_DGND2") (pintype "bidirectional"))
      (node (ref "LDO7") (pin "DGND3") (pinfunction "GND_DGND3") (pintype "bidirectional"))
      (node (ref "R6A") (pin "2") (pinfunction "2_2") (pintype "passive"))
      (node (ref "R6B") (pin "2") (pinfunction "2_2") (pintype "passive"))
      (node (ref "R6D") (pin "2") (pinfunction "2_2") (pintype "passive"))
      (node (ref "R7A") (pin "2") (pinfunction "2_2") (pintype "passive"))
      (node (ref "R7B") (pin "2") (pinfunction "2_2") (pintype "passive"))
      (node (ref "R7D") (pin "2") (pinfunction "2_2") (pintype "passive"))
      (node (ref "SH2") (pin "1") (pinfunction "P$1_1") (pintype "bidirectional"))
    )
    (net (code "29") (name "L+") (class "Default")
      (node (ref "R23O") (pin "1") (pinfunction "1_1") (pintype "passive"))
      (node (ref "R24O") (pin "1") (pinfunction "1_1") (pintype "passive"))
      (node (ref "R4") (pin "2") (pinfunction "2_2") (pintype "passive"))
    )
    (net (code "30") (name "L-") (class "Default")
      (node (ref "R25O") (pin "1") (pinfunction "1_1") (pintype "passive"))
      (node (ref "R26O") (pin "1") (pinfunction "1_1") (pintype "passive"))
      (node (ref "R3") (pin "2") (pinfunction "2_2") (pintype "passive"))
    )
    (net (code "31") (name "L_OUT") (class "Default")
      (node (ref "C21O1") (pin "1") (pinfunction "1_1") (pintype "passive"))
      (node (ref "C21O1") (pin "4") (pinfunction "1_4") (pintype "passive"))
      (node (ref "J3") (pin "2") (pinfunction "TIP_2") (pintype "bidirectional"))
      (node (ref "R20O2") (pin "2") (pinfunction "2_2") (pintype "passive"))
      (node (ref "Z5") (pin "1") (pinfunction "C_1") (pintype "passive"))
    )
    (net (code "32") (name "Net-(C1P-+)") (class "Default")
      (node (ref "C1P") (pin "1") (pinfunction "+_1") (pintype "bidirectional"))
      (node (ref "D10") (pin "1") (pinfunction "K_1") (pintype "bidirectional"))
      (node (ref "D9") (pin "1") (pinfunction "K_1") (pintype "bidirectional"))
      (node (ref "J6") (pin "4") (pinfunction "4_4") (pintype "bidirectional"))
    )
    (net (code "33") (name "Net-(C1P1-+)") (class "Default")
      (node (ref "C1P1") (pin "1") (pinfunction "+_1") (pintype "bidirectional"))
      (node (ref "D13") (pin "1") (pinfunction "K_1") (pintype "bidirectional"))
      (node (ref "D14") (pin "1") (pinfunction "K_1") (pintype "bidirectional"))
      (node (ref "J6") (pin "10") (pinfunction "10_10") (pintype "bidirectional"))
    )
    (net (code "34") (name "Net-(C1P2-+)") (class "Default")
      (node (ref "C1P2") (pin "1") (pinfunction "+_1") (pintype "bidirectional"))
      (node (ref "D17") (pin "1") (pinfunction "K_1") (pintype "bidirectional"))
      (node (ref "D18") (pin "1") (pinfunction "K_1") (pintype "bidirectional"))
      (node (ref "J4") (pin "8") (pinfunction "8_8") (pintype "bidirectional"))
    )
    (net (code "35") (name "Net-(C1P3-+)") (class "Default")
      (node (ref "C1P3") (pin "1") (pinfunction "+_1") (pintype "bidirectional"))
      (node (ref "D21") (pin "1") (pinfunction "K_1") (pintype "bidirectional"))
      (node (ref "D22") (pin "1") (pinfunction "K_1") (pintype "bidirectional"))
      (node (ref "J4") (pin "2") (pinfunction "2_2") (pintype "bidirectional"))
    )
    (net (code "36") (name "Net-(C2O-Pad1)") (class "Default")
      (node (ref "C2O") (pin "1") (pinfunction "1_1") (pintype "passive"))
      (node (ref "R17") (pin "2") (pinfunction "2_2") (pintype "passive"))
      (node (ref "SX1") (pin "6") (pinfunction "6_6") (pintype "passive"))
    )
    (net (code "37") (name "Net-(C2O-Pad2)") (class "Default")
      (node (ref "C2O") (pin "2") (pinfunction "2_2") (pintype "passive"))
      (node (ref "R3O") (pin "1") (pinfunction "1_1") (pintype "passive"))
      (node (ref "R8") (pin "2") (pinfunction "2_2") (pintype "passive"))
    )
    (net (code "38") (name "Net-(C2O1-Pad1)") (class "Default")
      (node (ref "C2O1") (pin "1") (pinfunction "1_1") (pintype "passive"))
      (node (ref "R18") (pin "1") (pinfunction "1_1") (pintype "passive"))
      (node (ref "SX2") (pin "6") (pinfunction "6_6") (pintype "passive"))
    )
    (net (code "39") (name "Net-(C2O1-Pad2)") (class "Default")
      (node (ref "C2O1") (pin "2") (pinfunction "2_2") (pintype "passive"))
      (node (ref "R14") (pin "2") (pinfunction "2_2") (pintype "passive"))
      (node (ref "R3O1") (pin "1") (pinfunction "1_1") (pintype "passive"))
    )
    (net (code "40") (name "Net-(C2P-+)") (class "Default")
      (node (ref "C2P") (pin "1") (pinfunction "+_1") (pintype "bidirectional"))
      (node (ref "J6") (pin "5") (pinfunction "5_5") (pintype "bidirectional"))
      (node (ref "R6P") (pin "2") (pinfunction "2_2") (pintype "passive"))
    )
    (net (code "41") (name "Net-(C2P1-+)") (class "Default")
      (node (ref "C2P1") (pin "1") (pinfunction "+_1") (pintype "bidirectional"))
      (node (ref "J6") (pin "11") (pinfunction "11_11") (pintype "bidirectional"))
      (node (ref "R6P1") (pin "2") (pinfunction "2_2") (pintype "passive"))
    )
    (net (code "42") (name "Net-(C2P2-+)") (class "Default")
      (node (ref "C2P2") (pin "1") (pinfunction "+_1") (pintype "bidirectional"))
      (node (ref "J4") (pin "7") (pinfunction "7_7") (pintype "bidirectional"))
      (node (ref "R6P2") (pin "2") (pinfunction "2_2") (pintype "passive"))
    )
    (net (code "43") (name "Net-(C2P3-+)") (class "Default")
      (node (ref "C2P3") (pin "1") (pinfunction "+_1") (pintype "bidirectional"))
      (node (ref "J4") (pin "1") (pinfunction "1_1") (pintype "bidirectional"))
      (node (ref "R6P3") (pin "2") (pinfunction "2_2") (pintype "passive"))
    )
    (net (code "44") (name "Net-(C4P-+)") (class "Default")
      (node (ref "C4P") (pin "1") (pinfunction "+_1") (pintype "bidirectional"))
      (node (ref "R2P") (pin "1") (pinfunction "1_1") (pintype "passive"))
      (node (ref "R3P") (pin "2") (pinfunction "2_2") (pintype "passive"))
      (node (ref "R4P") (pin "1") (pinfunction "1_1") (pintype "passive"))
      (node (ref "R5P") (pin "2") (pinfunction "2_2") (pintype "passive"))
    )
    (net (code "45") (name "Net-(C4P1-+)") (class "Default")
      (node (ref "C4P1") (pin "1") (pinfunction "+_1") (pintype "bidirectional"))
      (node (ref "R2P1") (pin "1") (pinfunction "1_1") (pintype "passive"))
      (node (ref "R3P1") (pin "2") (pinfunction "2_2") (pintype "passive"))
      (node (ref "R4P1") (pin "1") (pinfunction "1_1") (pintype "passive"))
      (node (ref "R5P1") (pin "2") (pinfunction "2_2") (pintype "passive"))
    )
    (net (code "46") (name "Net-(C11O-+)") (class "Default")
      (node (ref "C11O") (pin "1") (pinfunction "+_1") (pintype "passive"))
      (node (ref "J13") (pin "6") (pinfunction "6_6") (pintype "passive"))
    )
    (net (code "47") (name "Net-(C11O--)") (class "Default")
      (node (ref "C11O") (pin "2") (pinfunction "-_2") (pintype "passive"))
      (node (ref "R12O") (pin "2") (pinfunction "2_2") (pintype "passive"))
      (node (ref "R19O") (pin "2") (pinfunction "2_2") (pintype "passive"))
    )
    (net (code "48") (name "Net-(C12O-+)") (class "Default")
      (node (ref "C12O") (pin "1") (pinfunction "+_1") (pintype "passive"))
      (node (ref "J13") (pin "1") (pinfunction "1_1") (pintype "passive"))
    )
    (net (code "49") (name "Net-(C12O--)") (class "Default")
      (node (ref "C12O") (pin "2") (pinfunction "-_2") (pintype "passive"))
      (node (ref "R18O") (pin "2") (pinfunction "2_2") (pintype "passive"))
      (node (ref "R20O") (pin "1") (pinfunction "1_1") (pintype "passive"))
    )
    (net (code "50") (name "Net-(C13O-+)") (class "Default")
      (node (ref "C13O") (pin "1") (pinfunction "+_1") (pintype "passive"))
      (node (ref "J13") (pin "4") (pinfunction "4_4") (pintype "passive"))
    )
    (net (code "51") (name "Net-(C13O--)") (class "Default")
      (node (ref "C13O") (pin "2") (pinfunction "-_2") (pintype "passive"))
      (node (ref "R14O") (pin "2") (pinfunction "2_2") (pintype "passive"))
      (node (ref "R21O") (pin "2") (pinfunction "2_2") (pintype "passive"))
    )
    (net (code "52") (name "Net-(C14O-+)") (class "Default")
      (node (ref "C14O") (pin "1") (pinfunction "+_1") (pintype "passive"))
      (node (ref "J13") (pin "3") (pinfunction "3_3") (pintype "passive"))
    )
    (net (code "53") (name "Net-(C14O--)") (class "Default")
      (node (ref "C14O") (pin "2") (pinfunction "-_2") (pintype "passive"))
      (node (ref "R11O") (pin "1") (pinfunction "1_1") (pintype "passive"))
      (node (ref "R16O") (pin "2") (pinfunction "2_2") (pintype "passive"))
    )
    (net (code "54") (name "Net-(C15O-+)") (class "Default")
      (node (ref "C15O") (pin "1") (pinfunction "+_1") (pintype "passive"))
      (node (ref "J2") (pin "6") (pinfunction "6_6") (pintype "passive"))
    )
    (net (code "55") (name "Net-(C15O--)") (class "Default")
      (node (ref "C15O") (pin "2") (pinfunction "-_2") (pintype "passive"))
      (node (ref "R24O") (pin "2") (pinfunction "2_2") (pintype "passive"))
      (node (ref "R28O") (pin "2") (pinfunction "2_2") (pintype "passive"))
    )
    (net (code "56") (name "Net-(C24O-+)") (class "Default")
      (node (ref "C24O") (pin "1") (pinfunction "+_1") (pintype "passive"))
      (node (ref "J2") (pin "1") (pinfunction "1_1") (pintype "passive"))
    )
    (net (code "57") (name "Net-(C24O--)") (class "Default")
      (node (ref "C24O") (pin "2") (pinfunction "-_2") (pintype "passive"))
      (node (ref "R23O") (pin "2") (pinfunction "2_2") (pintype "passive"))
      (node (ref "R29O") (pin "1") (pinfunction "1_1") (pintype "passive"))
    )
    (net (code "58") (name "Net-(C25O-+)") (class "Default")
      (node (ref "C25O") (pin "1") (pinfunction "+_1") (pintype "passive"))
      (node (ref "J2") (pin "4") (pinfunction "4_4") (pintype "passive"))
    )
    (net (code "59") (name "Net-(C25O--)") (class "Default")
      (node (ref "C25O") (pin "2") (pinfunction "-_2") (pintype "passive"))
      (node (ref "R25O") (pin "2") (pinfunction "2_2") (pintype "passive"))
      (node (ref "R30O") (pin "2") (pinfunction "2_2") (pintype "passive"))
    )
    (net (code "60") (name "Net-(C26O-+)") (class "Default")
      (node (ref "C26O") (pin "1") (pinfunction "+_1") (pintype "passive"))
      (node (ref "J2") (pin "3") (pinfunction "3_3") (pintype "passive"))
    )
    (net (code "61") (name "Net-(C26O--)") (class "Default")
      (node (ref "C26O") (pin "2") (pinfunction "-_2") (pintype "passive"))
      (node (ref "R22O") (pin "1") (pinfunction "1_1") (pintype "passive"))
      (node (ref "R26O") (pin "2") (pinfunction "2_2") (pintype "passive"))
    )
    (net (code "62") (name "Net-(D1-A)") (class "Default")
      (node (ref "D1") (pin "2") (pinfunction "A_2") (pintype "passive"))
      (node (ref "R1") (pin "1") (pinfunction "1_1") (pintype "passive"))
      (node (ref "SX3") (pin "2") (pinfunction "2_2") (pintype "passive"))
    )
    (net (code "63") (name "Net-(D1-C)") (class "Default")
      (node (ref "D1") (pin "1") (pinfunction "C_1") (pintype "passive"))
      (node (ref "D2") (pin "1") (pinfunction "C_1") (pintype "passive"))
      (node (ref "SX3") (pin "3") (pinfunction "3_3") (pintype "passive"))
      (node (ref "SX3") (pin "8") (pinfunction "8_8") (pintype "passive"))
      (node (ref "U1") (pin "3") (pinfunction "IN_3") (pintype "input"))
    )
    (net (code "64") (name "Net-(D2-A)") (class "Default")
      (node (ref "D2") (pin "2") (pinfunction "A_2") (pintype "passive"))
      (node (ref "R2") (pin "1") (pinfunction "1_1") (pintype "passive"))
      (node (ref "SX3") (pin "7") (pinfunction "7_7") (pintype "passive"))
    )
    (net (code "65") (name "Net-(D3-A)") (class "Default")
      (node (ref "D3") (pin "2") (pinfunction "A_2") (pintype "passive"))
      (node (ref "R7") (pin "1") (pinfunction "1_1") (pintype "passive"))
      (node (ref "SX1") (pin "7") (pinfunction "7_7") (pintype "passive"))
    )
    (net (code "66") (name "Net-(D3-C)") (class "Default")
      (node (ref "C21O") (pin "2") (pinfunction "2_2") (pintype "passive"))
      (node (ref "C21O") (pin "3") (pinfunction "2_3") (pintype "passive"))
      (node (ref "D3") (pin "1") (pinfunction "C_1") (pintype "passive"))
      (node (ref "SX1") (pin "1") (pinfunction "1_1") (pintype "passive"))
      (node (ref "SX1") (pin "8") (pinfunction "8_8") (pintype "passive"))
    )
    (net (code "67") (name "Net-(D4-A)") (class "Default")
      (node (ref "D4") (pin "2") (pinfunction "A_2") (pintype "passive"))
      (node (ref "R3") (pin "1") (pinfunction "1_1") (pintype "passive"))
      (node (ref "SX4") (pin "2") (pinfunction "2_2") (pintype "passive"))
    )
    (net (code "68") (name "Net-(D4-C)") (class "Default")
      (node (ref "D4") (pin "1") (pinfunction "C_1") (pintype "passive"))
      (node (ref "D5") (pin "1") (pinfunction "C_1") (pintype "passive"))
      (node (ref "SX4") (pin "3") (pinfunction "3_3") (pintype "passive"))
      (node (ref "SX4") (pin "8") (pinfunction "8_8") (pintype "passive"))
      (node (ref "U2") (pin "3") (pinfunction "IN_3") (pintype "input"))
    )
    (net (code "69") (name "Net-(D5-A)") (class "Default")
      (node (ref "D5") (pin "2") (pinfunction "A_2") (pintype "passive"))
      (node (ref "R4") (pin "1") (pinfunction "1_1") (pintype "passive"))
      (node (ref "SX4") (pin "7") (pinfunction "7_7") (pintype "passive"))
    )
    (net (code "70") (name "Net-(D6-A)") (class "Default")
      (node (ref "D6") (pin "2") (pinfunction "A_2") (pintype "passive"))
      (node (ref "R13") (pin "1") (pinfunction "1_1") (pintype "passive"))
      (node (ref "SX2") (pin "7") (pinfunction "7_7") (pintype "passive"))
    )
    (net (code "71") (name "Net-(D6-C)") (class "Default")
      (node (ref "C21O1") (pin "2") (pinfunction "2_2") (pintype "passive"))
      (node (ref "C21O1") (pin "3") (pinfunction "2_3") (pintype "passive"))
      (node (ref "D6") (pin "1") (pinfunction "C_1") (pintype "passive"))
      (node (ref "SX2") (pin "1") (pinfunction "1_1") (pintype "passive"))
      (node (ref "SX2") (pin "8") (pinfunction "8_8") (pintype "passive"))
    )
    (net (code "72") (name "Net-(IC1-ILIM)") (class "Default")
      (node (ref "IC1") (pin "5") (pinfunction "ILIM_5") (pintype "bidirectional"))
      (node (ref "J1") (pin "2") (pinfunction "2_2") (pintype "bidirectional"))
      (node (ref "R6D") (pin "1") (pinfunction "1_1") (pintype "passive"))
    )
    (net (code "73") (name "Net-(IC1-PG)") (class "Default")
      (node (ref "IC1") (pin "4") (pinfunction "PG_4") (pintype "bidirectional"))
      (node (ref "J1") (pin "1") (pinfunction "1_1") (pintype "bidirectional"))
      (node (ref "R8D") (pin "2") (pinfunction "2_2") (pintype "passive"))
    )
    (net (code "74") (name "Net-(IC1-PGFB)") (class "Default")
      (node (ref "IC1") (pin "6") (pinfunction "PGFB_6") (pintype "bidirectional"))
      (node (ref "J1") (pin "3") (pinfunction "3_3") (pintype "bidirectional"))
    )
    (net (code "75") (name "Net-(IC1-SET)") (class "Default")
      (node (ref "C19D") (pin "1") (pinfunction "1_1") (pintype "passive"))
      (node (ref "IC1") (pin "7") (pinfunction "SET_7") (pintype "bidirectional"))
      (node (ref "J1") (pin "4") (pinfunction "4_4") (pintype "bidirectional"))
      (node (ref "R7D") (pin "1") (pinfunction "1_1") (pintype "passive"))
    )
    (net (code "76") (name "Net-(IC2-ILIM)") (class "Default")
      (node (ref "IC2") (pin "5") (pinfunction "ILIM_5") (pintype "bidirectional"))
      (node (ref "J5") (pin "2") (pinfunction "2_2") (pintype "bidirectional"))
      (node (ref "R6A") (pin "1") (pinfunction "1_1") (pintype "passive"))
    )
    (net (code "77") (name "Net-(IC2-PG)") (class "Default")
      (node (ref "IC2") (pin "4") (pinfunction "PG_4") (pintype "bidirectional"))
      (node (ref "J5") (pin "1") (pinfunction "1_1") (pintype "bidirectional"))
      (node (ref "R8A") (pin "2") (pinfunction "2_2") (pintype "passive"))
    )
    (net (code "78") (name "Net-(IC2-PGFB)") (class "Default")
      (node (ref "IC2") (pin "6") (pinfunction "PGFB_6") (pintype "bidirectional"))
      (node (ref "J5") (pin "3") (pinfunction "3_3") (pintype "bidirectional"))
    )
    (net (code "79") (name "Net-(IC2-SET)") (class "Default")
      (node (ref "C19A") (pin "1") (pinfunction "1_1") (pintype "passive"))
      (node (ref "IC2") (pin "7") (pinfunction "SET_7") (pintype "bidirectional"))
      (node (ref "J5") (pin "4") (pinfunction "4_4") (pintype "bidirectional"))
      (node (ref "R7A") (pin "1") (pinfunction "1_1") (pintype "passive"))
    )
    (net (code "80") (name "Net-(IC5-ILIM)") (class "Default")
      (node (ref "IC5") (pin "5") (pinfunction "ILIM_5") (pintype "bidirectional"))
      (node (ref "J17") (pin "2") (pinfunction "2_2") (pintype "bidirectional"))
      (node (ref "R6B") (pin "1") (pinfunction "1_1") (pintype "passive"))
    )
    (net (code "81") (name "Net-(IC5-PG)") (class "Default")
      (node (ref "IC5") (pin "4") (pinfunction "PG_4") (pintype "bidirectional"))
      (node (ref "J17") (pin "1") (pinfunction "1_1") (pintype "bidirectional"))
      (node (ref "R8B") (pin "2") (pinfunction "2_2") (pintype "passive"))
    )
    (net (code "82") (name "Net-(IC5-PGFB)") (class "Default")
      (node (ref "IC5") (pin "6") (pinfunction "PGFB_6") (pintype "bidirectional"))
      (node (ref "J17") (pin "3") (pinfunction "3_3") (pintype "bidirectional"))
    )
    (net (code "83") (name "Net-(IC5-SET)") (class "Default")
      (node (ref "C19B") (pin "1") (pinfunction "1_1") (pintype "passive"))
      (node (ref "IC5") (pin "7") (pinfunction "SET_7") (pintype "bidirectional"))
      (node (ref "J17") (pin "4") (pinfunction "4_4") (pintype "bidirectional"))
      (node (ref "R7B") (pin "1") (pinfunction "1_1") (pintype "passive"))
    )
    (net (code "84") (name "Net-(IC6-ILIM)") (class "Default")
      (node (ref "IC6") (pin "5") (pinfunction "ILIM_5") (pintype "bidirectional"))
      (node (ref "J8") (pin "2") (pinfunction "2_2") (pintype "bidirectional"))
      (node (ref "R6B2") (pin "1") (pinfunction "1_1") (pintype "passive"))
    )
    (net (code "85") (name "Net-(IC6-PG)") (class "Default")
      (node (ref "IC6") (pin "4") (pinfunction "PG_4") (pintype "bidirectional"))
      (node (ref "J8") (pin "1") (pinfunction "1_1") (pintype "bidirectional"))
      (node (ref "R8B2") (pin "2") (pinfunction "2_2") (pintype "passive"))
    )
    (net (code "86") (name "Net-(IC6-PGFB)") (class "Default")
      (node (ref "IC6") (pin "6") (pinfunction "PGFB_6") (pintype "bidirectional"))
      (node (ref "J8") (pin "3") (pinfunction "3_3") (pintype "bidirectional"))
    )
    (net (code "87") (name "Net-(IC6-SET)") (class "Default")
      (node (ref "C19B2") (pin "1") (pinfunction "1_1") (pintype "passive"))
      (node (ref "IC6") (pin "7") (pinfunction "SET_7") (pintype "bidirectional"))
      (node (ref "J8") (pin "4") (pinfunction "4_4") (pintype "bidirectional"))
      (node (ref "R7B2") (pin "1") (pinfunction "1_1") (pintype "passive"))
    )
    (net (code "88") (name "Net-(IC8-ILIM)") (class "Default")
      (node (ref "IC8") (pin "5") (pinfunction "ILIM_5") (pintype "bidirectional"))
      (node (ref "J10") (pin "2") (pinfunction "2_2") (pintype "bidirectional"))
      (node (ref "R6B4") (pin "1") (pinfunction "1_1") (pintype "passive"))
    )
    (net (code "89") (name "Net-(IC8-PG)") (class "Default")
      (node (ref "IC8") (pin "4") (pinfunction "PG_4") (pintype "bidirectional"))
      (node (ref "J10") (pin "1") (pinfunction "1_1") (pintype "bidirectional"))
      (node (ref "R8B4") (pin "2") (pinfunction "2_2") (pintype "passive"))
    )
    (net (code "90") (name "Net-(IC8-PGFB)") (class "Default")
      (node (ref "IC8") (pin "6") (pinfunction "PGFB_6") (pintype "bidirectional"))
      (node (ref "J10") (pin "3") (pinfunction "3_3") (pintype "bidirectional"))
    )
    (net (code "91") (name "Net-(IC8-SET)") (class "Default")
      (node (ref "C19B4") (pin "1") (pinfunction "1_1") (pintype "passive"))
      (node (ref "IC8") (pin "7") (pinfunction "SET_7") (pintype "bidirectional"))
      (node (ref "J10") (pin "4") (pinfunction "4_4") (pintype "bidirectional"))
      (node (ref "R7B4") (pin "1") (pinfunction "1_1") (pintype "passive"))
    )
    (net (code "92") (name "Net-(IC10-ILIM)") (class "Default")
      (node (ref "IC10") (pin "5") (pinfunction "ILIM_5") (pintype "bidirectional"))
      (node (ref "J12") (pin "2") (pinfunction "2_2") (pintype "bidirectional"))
      (node (ref "R6B6") (pin "1") (pinfunction "1_1") (pintype "passive"))
    )
    (net (code "93") (name "Net-(IC10-PG)") (class "Default")
      (node (ref "IC10") (pin "4") (pinfunction "PG_4") (pintype "bidirectional"))
      (node (ref "J12") (pin "1") (pinfunction "1_1") (pintype "bidirectional"))
      (node (ref "R8B6") (pin "2") (pinfunction "2_2") (pintype "passive"))
    )
    (net (code "94") (name "Net-(IC10-PGFB)") (class "Default")
      (node (ref "IC10") (pin "6") (pinfunction "PGFB_6") (pintype "bidirectional"))
      (node (ref "J12") (pin "3") (pinfunction "3_3") (pintype "bidirectional"))
    )
    (net (code "95") (name "Net-(IC10-SET)") (class "Default")
      (node (ref "C19B6") (pin "1") (pinfunction "1_1") (pintype "passive"))
      (node (ref "IC10") (pin "7") (pinfunction "SET_7") (pintype "bidirectional"))
      (node (ref "J12") (pin "4") (pinfunction "4_4") (pintype "bidirectional"))
      (node (ref "R7B6") (pin "1") (pinfunction "1_1") (pintype "passive"))
    )
    (net (code "96") (name "Net-(R5-Pad1)") (class "Default")
      (node (ref "R5") (pin "1") (pinfunction "1_1") (pintype "passive"))
      (node (ref "SX3") (pin "1") (pinfunction "1_1") (pintype "passive"))
    )
    (net (code "97") (name "Net-(R11-Pad1)") (class "Default")
      (node (ref "R11") (pin "1") (pinfunction "1_1") (pintype "passive"))
      (node (ref "SX4") (pin "1") (pinfunction "1_1") (pintype "passive"))
    )
    (net (code "98") (name "Net-(R13-Pad2)") (class "Default")
      (node (ref "R13") (pin "2") (pinfunction "2_2") (pintype "passive"))
      (node (ref "R20") (pin "2") (pinfunction "2_2") (pintype "passive"))
      (node (ref "SX4") (pin "6") (pinfunction "6_6") (pintype "passive"))
    )
    (net (code "99") (name "Net-(R19-Pad1)") (class "Default")
      (node (ref "R19") (pin "1") (pinfunction "1_1") (pintype "passive"))
      (node (ref "R7") (pin "2") (pinfunction "2_2") (pintype "passive"))
      (node (ref "SX3") (pin "6") (pinfunction "6_6") (pintype "passive"))
    )
    (net (code "100") (name "Net-(U1-OUT)") (class "Default")
      (node (ref "R10") (pin "2") (pinfunction "2_2") (pintype "passive"))
      (node (ref "U1") (pin "2") (pinfunction "OUT_2") (pintype "passive"))
    )
    (net (code "101") (name "Net-(U2-OUT)") (class "Default")
      (node (ref "R16") (pin "2") (pinfunction "2_2") (pintype "passive"))
      (node (ref "U2") (pin "2") (pinfunction "OUT_2") (pintype "passive"))
    )
    (net (code "102") (name "Net-(Z1-A)") (class "Default")
      (node (ref "Z1") (pin "2") (pinfunction "A_2") (pintype "passive"))
      (node (ref "Z2") (pin "2") (pinfunction "A_2") (pintype "passive"))
    )
    (net (code "103") (name "Net-(Z3-A)") (class "Default")
      (node (ref "R8") (pin "1") (pinfunction "1_1") (pintype "passive"))
      (node (ref "SX1") (pin "2") (pinfunction "2_2") (pintype "passive"))
      (node (ref "Z3") (pin "2") (pinfunction "A_2") (pintype "passive"))
    )
    (net (code "104") (name "Net-(Z3-C)") (class "Default")
      (node (ref "R9") (pin "2") (pinfunction "2_2") (pintype "passive"))
      (node (ref "SX1") (pin "3") (pinfunction "3_3") (pintype "passive"))
      (node (ref "Z3") (pin "1") (pinfunction "C_1") (pintype "passive"))
    )
    (net (code "105") (name "Net-(Z4-A)") (class "Default")
      (node (ref "R14") (pin "1") (pinfunction "1_1") (pintype "passive"))
      (node (ref "SX2") (pin "2") (pinfunction "2_2") (pintype "passive"))
      (node (ref "Z4") (pin "2") (pinfunction "A_2") (pintype "passive"))
    )
    (net (code "106") (name "Net-(Z4-C)") (class "Default")
      (node (ref "R15") (pin "2") (pinfunction "2_2") (pintype "passive"))
      (node (ref "SX2") (pin "3") (pinfunction "3_3") (pintype "passive"))
      (node (ref "Z4") (pin "1") (pinfunction "C_1") (pintype "passive"))
    )
    (net (code "107") (name "Net-(Z5-A)") (class "Default")
      (node (ref "Z5") (pin "2") (pinfunction "A_2") (pintype "passive"))
      (node (ref "Z6") (pin "2") (pinfunction "A_2") (pintype "passive"))
    )
    (net (code "108") (name "PE") (class "Default")
      (node (ref "J4") (pin "11") (pinfunction "11_11") (pintype "bidirectional"))
      (node (ref "J6") (pin "1") (pinfunction "1_1") (pintype "bidirectional"))
    )
    (net (code "109") (name "R+") (class "Default")
      (node (ref "R12O") (pin "1") (pinfunction "1_1") (pintype "passive"))
      (node (ref "R18O") (pin "1") (pinfunction "1_1") (pintype "passive"))
      (node (ref "R2") (pin "2") (pinfunction "2_2") (pintype "passive"))
    )
    (net (code "110") (name "R-") (class "Default")
      (node (ref "R1") (pin "2") (pinfunction "2_2") (pintype "passive"))
      (node (ref "R14O") (pin "1") (pinfunction "1_1") (pintype "passive"))
      (node (ref "R16O") (pin "1") (pinfunction "1_1") (pintype "passive"))
    )
    (net (code "111") (name "R_OUT") (class "Default")
      (node (ref "C21O") (pin "1") (pinfunction "1_1") (pintype "passive"))
      (node (ref "C21O") (pin "4") (pinfunction "1_4") (pintype "passive"))
      (node (ref "J3") (pin "3") (pinfunction "RING_3") (pintype "bidirectional"))
      (node (ref "R20O1") (pin "2") (pinfunction "2_2") (pintype "passive"))
      (node (ref "Z2") (pin "1") (pinfunction "C_1") (pintype "passive"))
    )
    (net (code "112") (name "VCC{slash}1") (class "Default")
      (node (ref "C20B2") (pin "1") (pinfunction "1_1") (pintype "passive"))
      (node (ref "C20B4") (pin "1") (pinfunction "1_1") (pintype "passive"))
      (node (ref "C20B6") (pin "1") (pinfunction "1_1") (pintype "passive"))
      (node (ref "C21B2") (pin "1") (pinfunction "1_1") (pintype "passive"))
      (node (ref "C21B4") (pin "1") (pinfunction "1_1") (pintype "passive"))
      (node (ref "C21B6") (pin "1") (pinfunction "1_1") (pintype "passive"))
      (node (ref "C3P3") (pin "1") (pinfunction "+_1") (pintype "bidirectional"))
      (node (ref "C5P3") (pin "1") (pinfunction "+_1") (pintype "bidirectional"))
      (node (ref "C6P3") (pin "1") (pinfunction "+_1") (pintype "bidirectional"))
      (node (ref "C7P3") (pin "1") (pinfunction "+_1") (pintype "bidirectional"))
      (node (ref "IC10") (pin "1") (pinfunction "IN_1") (pintype "bidirectional"))
      (node (ref "IC10") (pin "2") (pinfunction "IN_2") (pintype "bidirectional"))
      (node (ref "IC10") (pin "3") (pinfunction "EN/UV_3") (pintype "bidirectional"))
      (node (ref "IC4") (pin "3") (pinfunction "IN_3") (pintype "input"))
      (node (ref "IC6") (pin "1") (pinfunction "IN_1") (pintype "bidirectional"))
      (node (ref "IC6") (pin "2") (pinfunction "IN_2") (pintype "bidirectional"))
      (node (ref "IC6") (pin "3") (pinfunction "EN/UV_3") (pintype "bidirectional"))
      (node (ref "IC8") (pin "1") (pinfunction "IN_1") (pintype "bidirectional"))
      (node (ref "IC8") (pin "2") (pinfunction "IN_2") (pintype "bidirectional"))
      (node (ref "IC8") (pin "3") (pinfunction "EN/UV_3") (pintype "bidirectional"))
      (node (ref "J10") (pin "7") (pinfunction "7_7") (pintype "bidirectional"))
      (node (ref "J10") (pin "8") (pinfunction "8_8") (pintype "bidirectional"))
      (node (ref "J12") (pin "7") (pinfunction "7_7") (pintype "bidirectional"))
      (node (ref "J12") (pin "8") (pinfunction "8_8") (pintype "bidirectional"))
      (node (ref "J8") (pin "7") (pinfunction "7_7") (pintype "bidirectional"))
      (node (ref "J8") (pin "8") (pinfunction "8_8") (pintype "bidirectional"))
      (node (ref "R6P3") (pin "1") (pinfunction "1_1") (pintype "passive"))
      (node (ref "R8B2") (pin "1") (pinfunction "1_1") (pintype "passive"))
      (node (ref "R8B4") (pin "1") (pinfunction "1_1") (pintype "passive"))
      (node (ref "R8B6") (pin "1") (pinfunction "1_1") (pintype "passive"))
    )
    (net (code "113") (name "VCC{slash}2") (class "Default")
      (node (ref "C20B") (pin "1") (pinfunction "1_1") (pintype "passive"))
      (node (ref "C20D") (pin "1") (pinfunction "1_1") (pintype "passive"))
      (node (ref "C21B") (pin "1") (pinfunction "1_1") (pintype "passive"))
      (node (ref "C21D") (pin "1") (pinfunction "1_1") (pintype "passive"))
      (node (ref "C3P1") (pin "1") (pinfunction "+_1") (pintype "bidirectional"))
      (node (ref "C5P1") (pin "1") (pinfunction "+_1") (pintype "bidirectional"))
      (node (ref "C6P1") (pin "1") (pinfunction "+_1") (pintype "bidirectional"))
      (node (ref "C7P1") (pin "1") (pinfunction "+_1") (pintype "bidirectional"))
      (node (ref "IC1") (pin "1") (pinfunction "IN_1") (pintype "bidirectional"))
      (node (ref "IC1") (pin "2") (pinfunction "IN_2") (pintype "bidirectional"))
      (node (ref "IC1") (pin "3") (pinfunction "EN/UV_3") (pintype "bidirectional"))
      (node (ref "IC3") (pin "3") (pinfunction "IN_3") (pintype "input"))
      (node (ref "IC5") (pin "1") (pinfunction "IN_1") (pintype "bidirectional"))
      (node (ref "IC5") (pin "2") (pinfunction "IN_2") (pintype "bidirectional"))
      (node (ref "IC5") (pin "3") (pinfunction "EN/UV_3") (pintype "bidirectional"))
      (node (ref "J1") (pin "7") (pinfunction "7_7") (pintype "bidirectional"))
      (node (ref "J1") (pin "8") (pinfunction "8_8") (pintype "bidirectional"))
      (node (ref "J17") (pin "7") (pinfunction "7_7") (pintype "bidirectional"))
      (node (ref "J17") (pin "8") (pinfunction "8_8") (pintype "bidirectional"))
      (node (ref "R6P1") (pin "1") (pinfunction "1_1") (pintype "passive"))
      (node (ref "R8B") (pin "1") (pinfunction "1_1") (pintype "passive"))
      (node (ref "R8D") (pin "1") (pinfunction "1_1") (pintype "passive"))
    )
    (net (code "114") (name "unconnected-(IC3-ADJ-Pad1)") (class "Default")
      (node (ref "IC3") (pin "1") (pinfunction "ADJ_1") (pintype "input"))
    )
    (net (code "115") (name "unconnected-(IC4-ADJ-Pad1)") (class "Default")
      (node (ref "IC4") (pin "1") (pinfunction "ADJ_1") (pintype "input"))
    )
    (net (code "116") (name "unconnected-(LDO1-NC-Pad4)") (class "Default")
      (node (ref "LDO1") (pin "4") (pinfunction "NC_4") (pintype "no_connect"))
    )
    (net (code "117") (name "unconnected-(LDO7-NC-Pad4)") (class "Default")
      (node (ref "LDO7") (pin "4") (pinfunction "NC_4") (pintype "no_connect"))
    )
    (net (code "118") (name "unconnected-(SX1-Pad9)") (class "Default")
      (node (ref "SX1") (pin "9") (pinfunction "9_9") (pintype "passive"))
    )
    (net (code "119") (name "unconnected-(SX2-Pad9)") (class "Default")
      (node (ref "SX2") (pin "9") (pinfunction "9_9") (pintype "passive"))
    )
    (net (code "120") (name "unconnected-(SX3-Pad9)") (class "Default")
      (node (ref "SX3") (pin "9") (pinfunction "9_9") (pintype "passive"))
    )
    (net (code "121") (name "unconnected-(SX4-Pad9)") (class "Default")
      (node (ref "SX4") (pin "9") (pinfunction "9_9") (pintype "passive"))
    )
  )
)
